# rtiduino.net
KiCad netlist of a schematic drawn in EAGLE
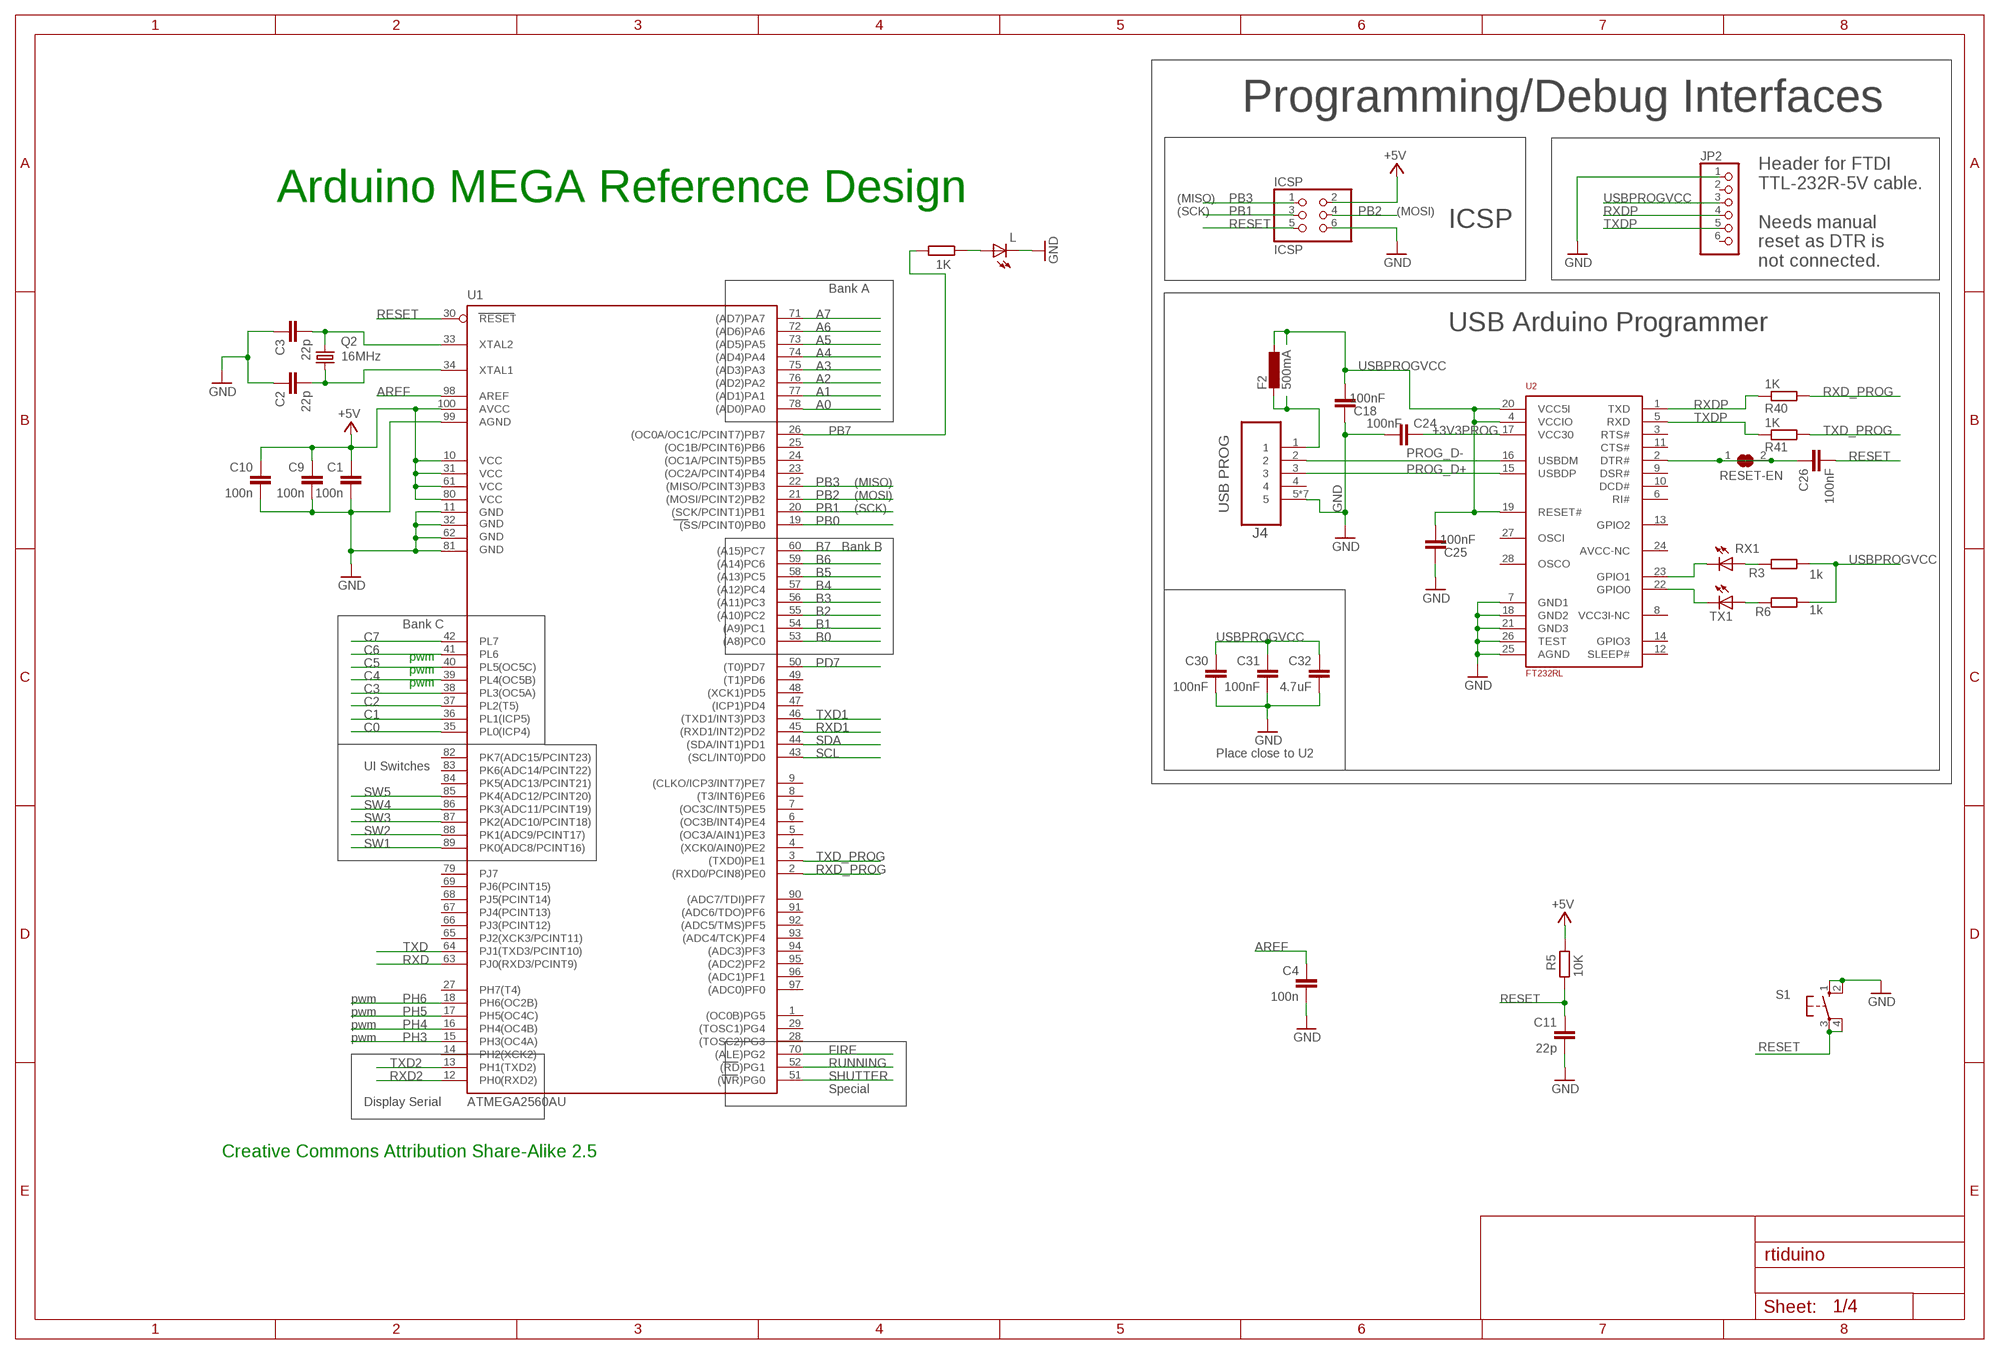
[diagram p0: schematic, sheet 1]
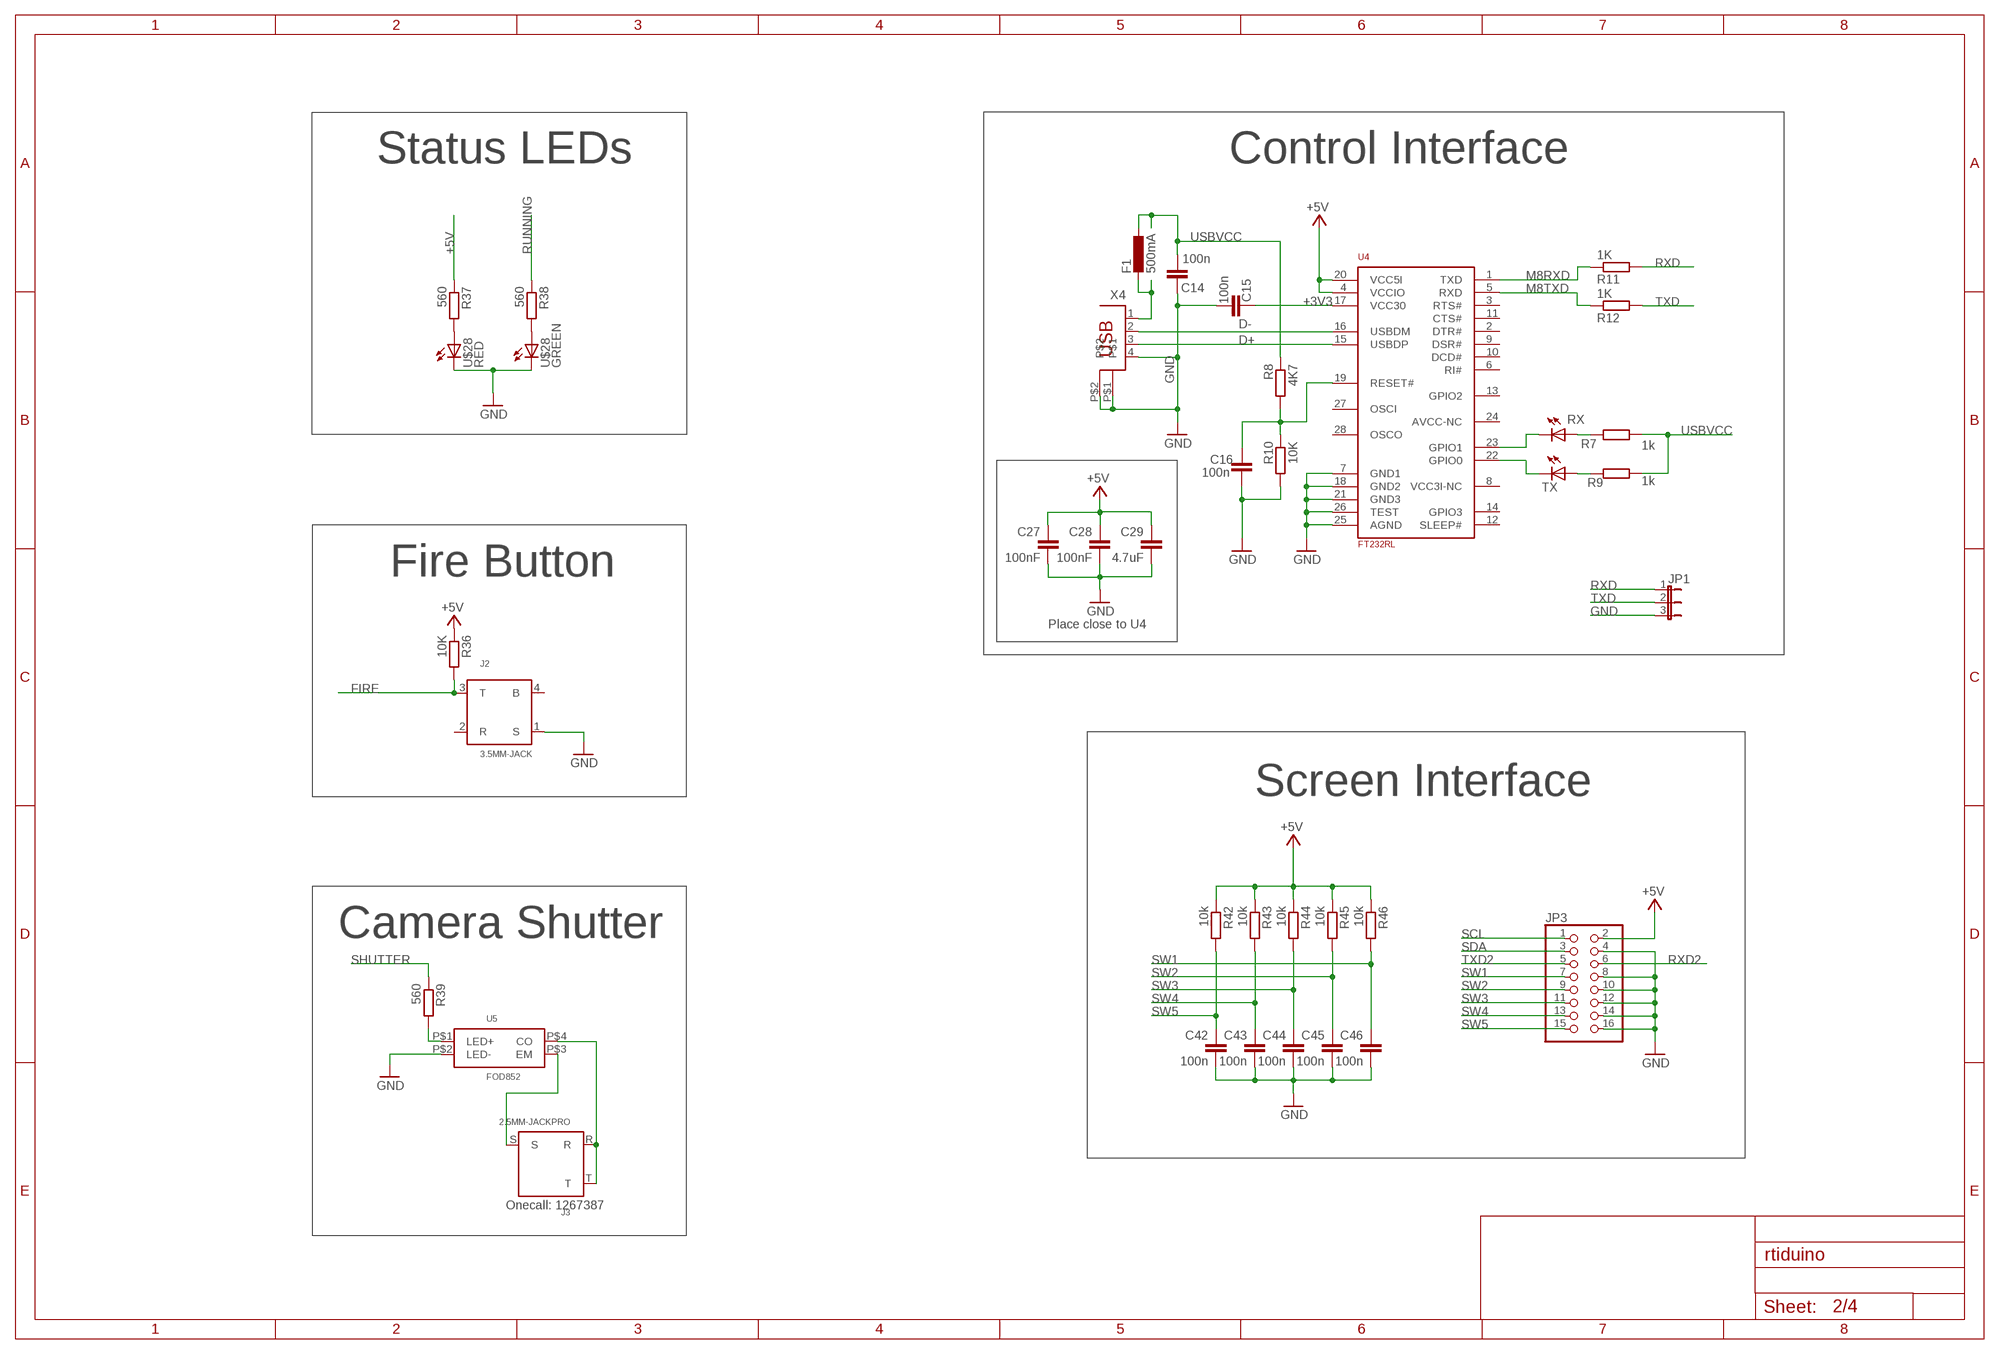
[diagram p1: schematic, sheet 2]
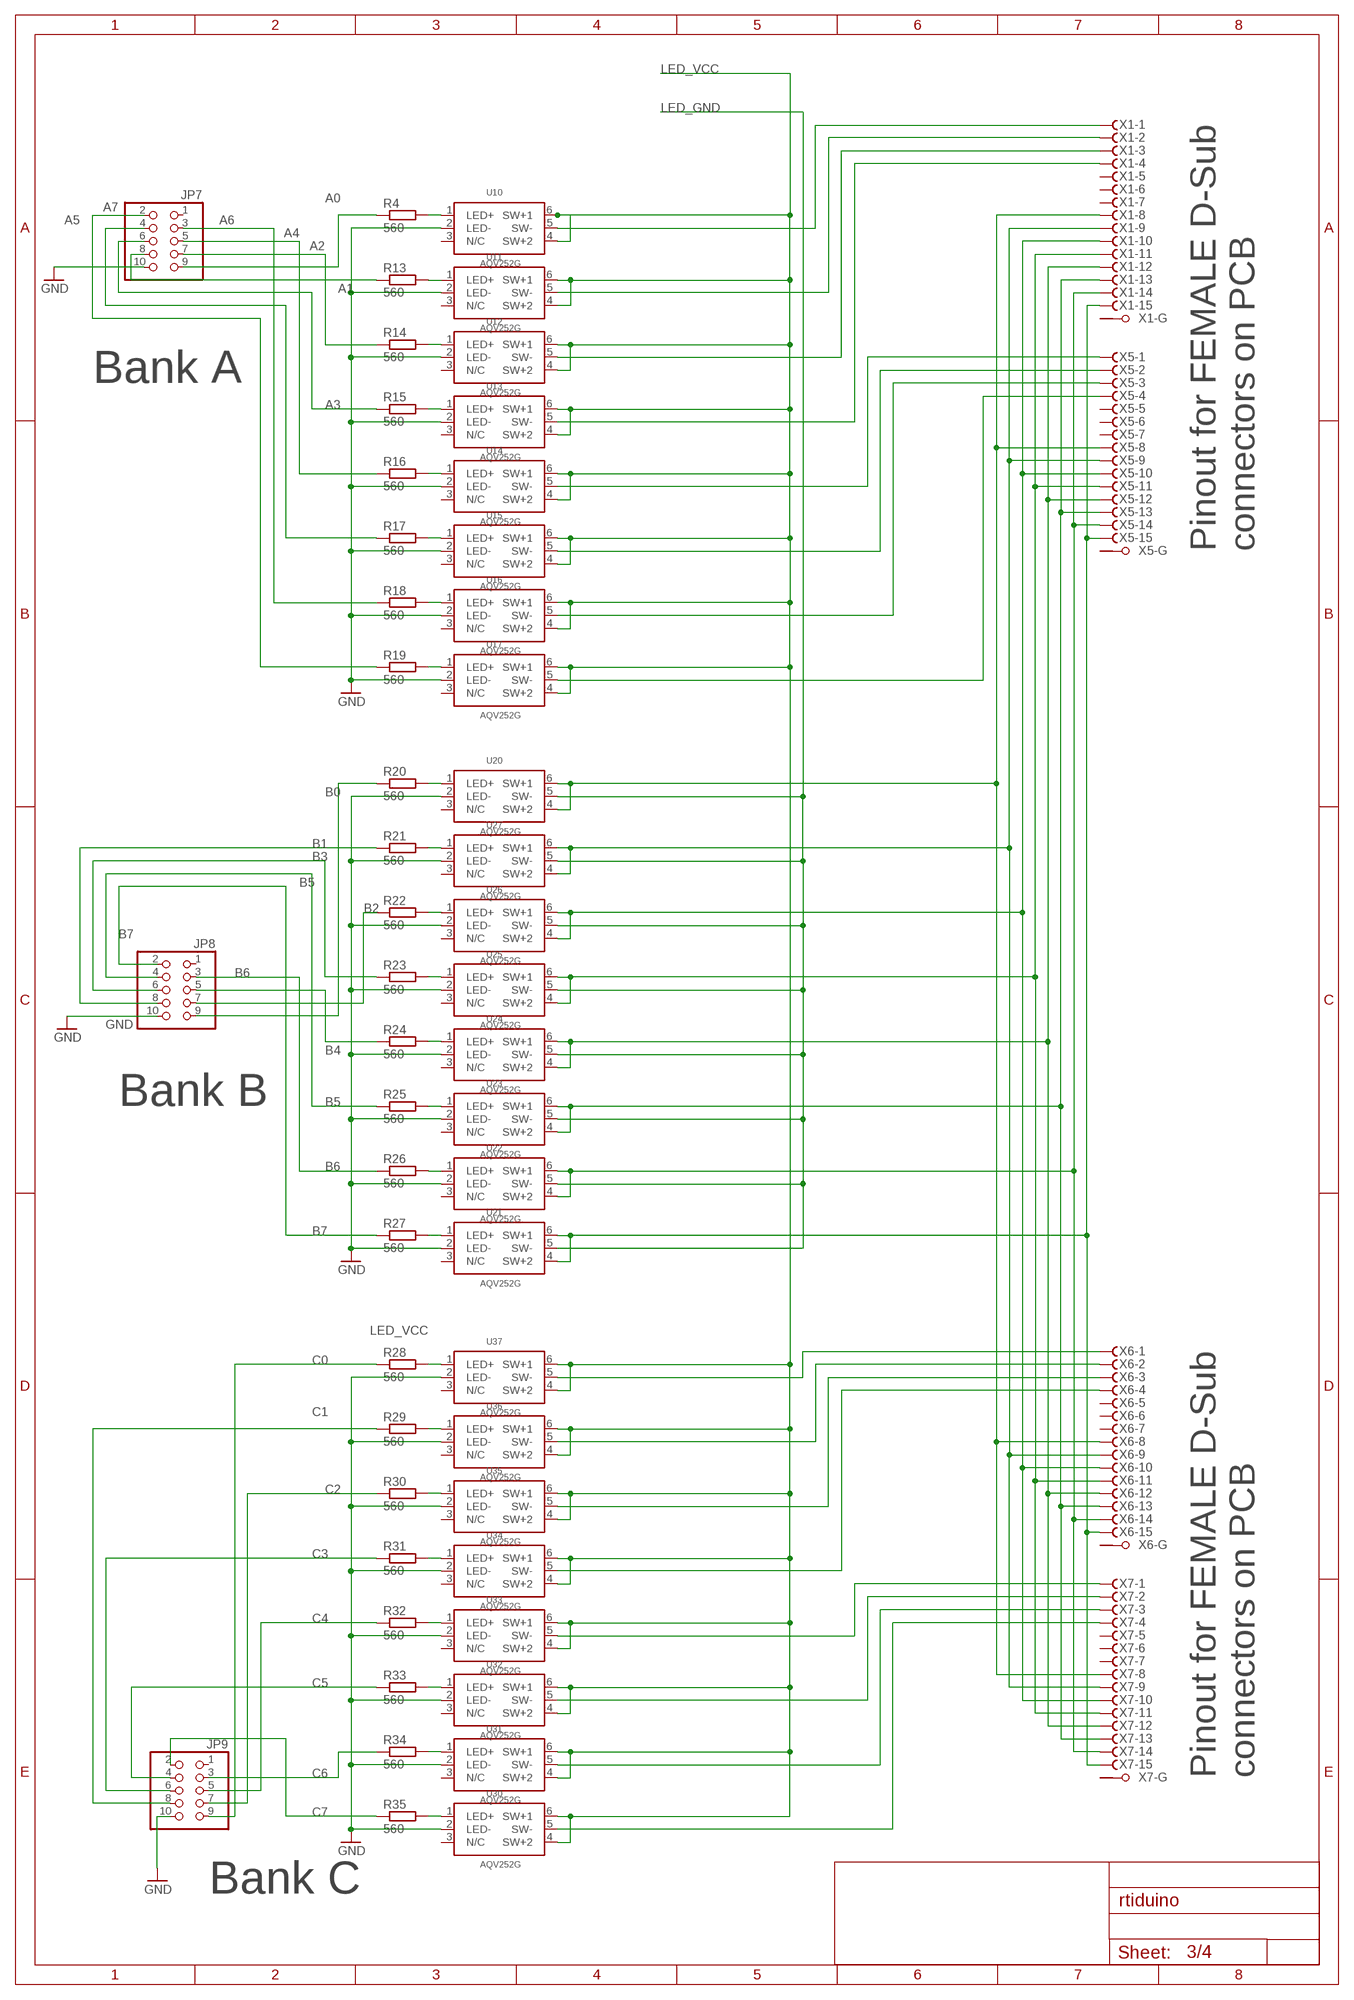
[diagram p2: schematic, sheet 3]
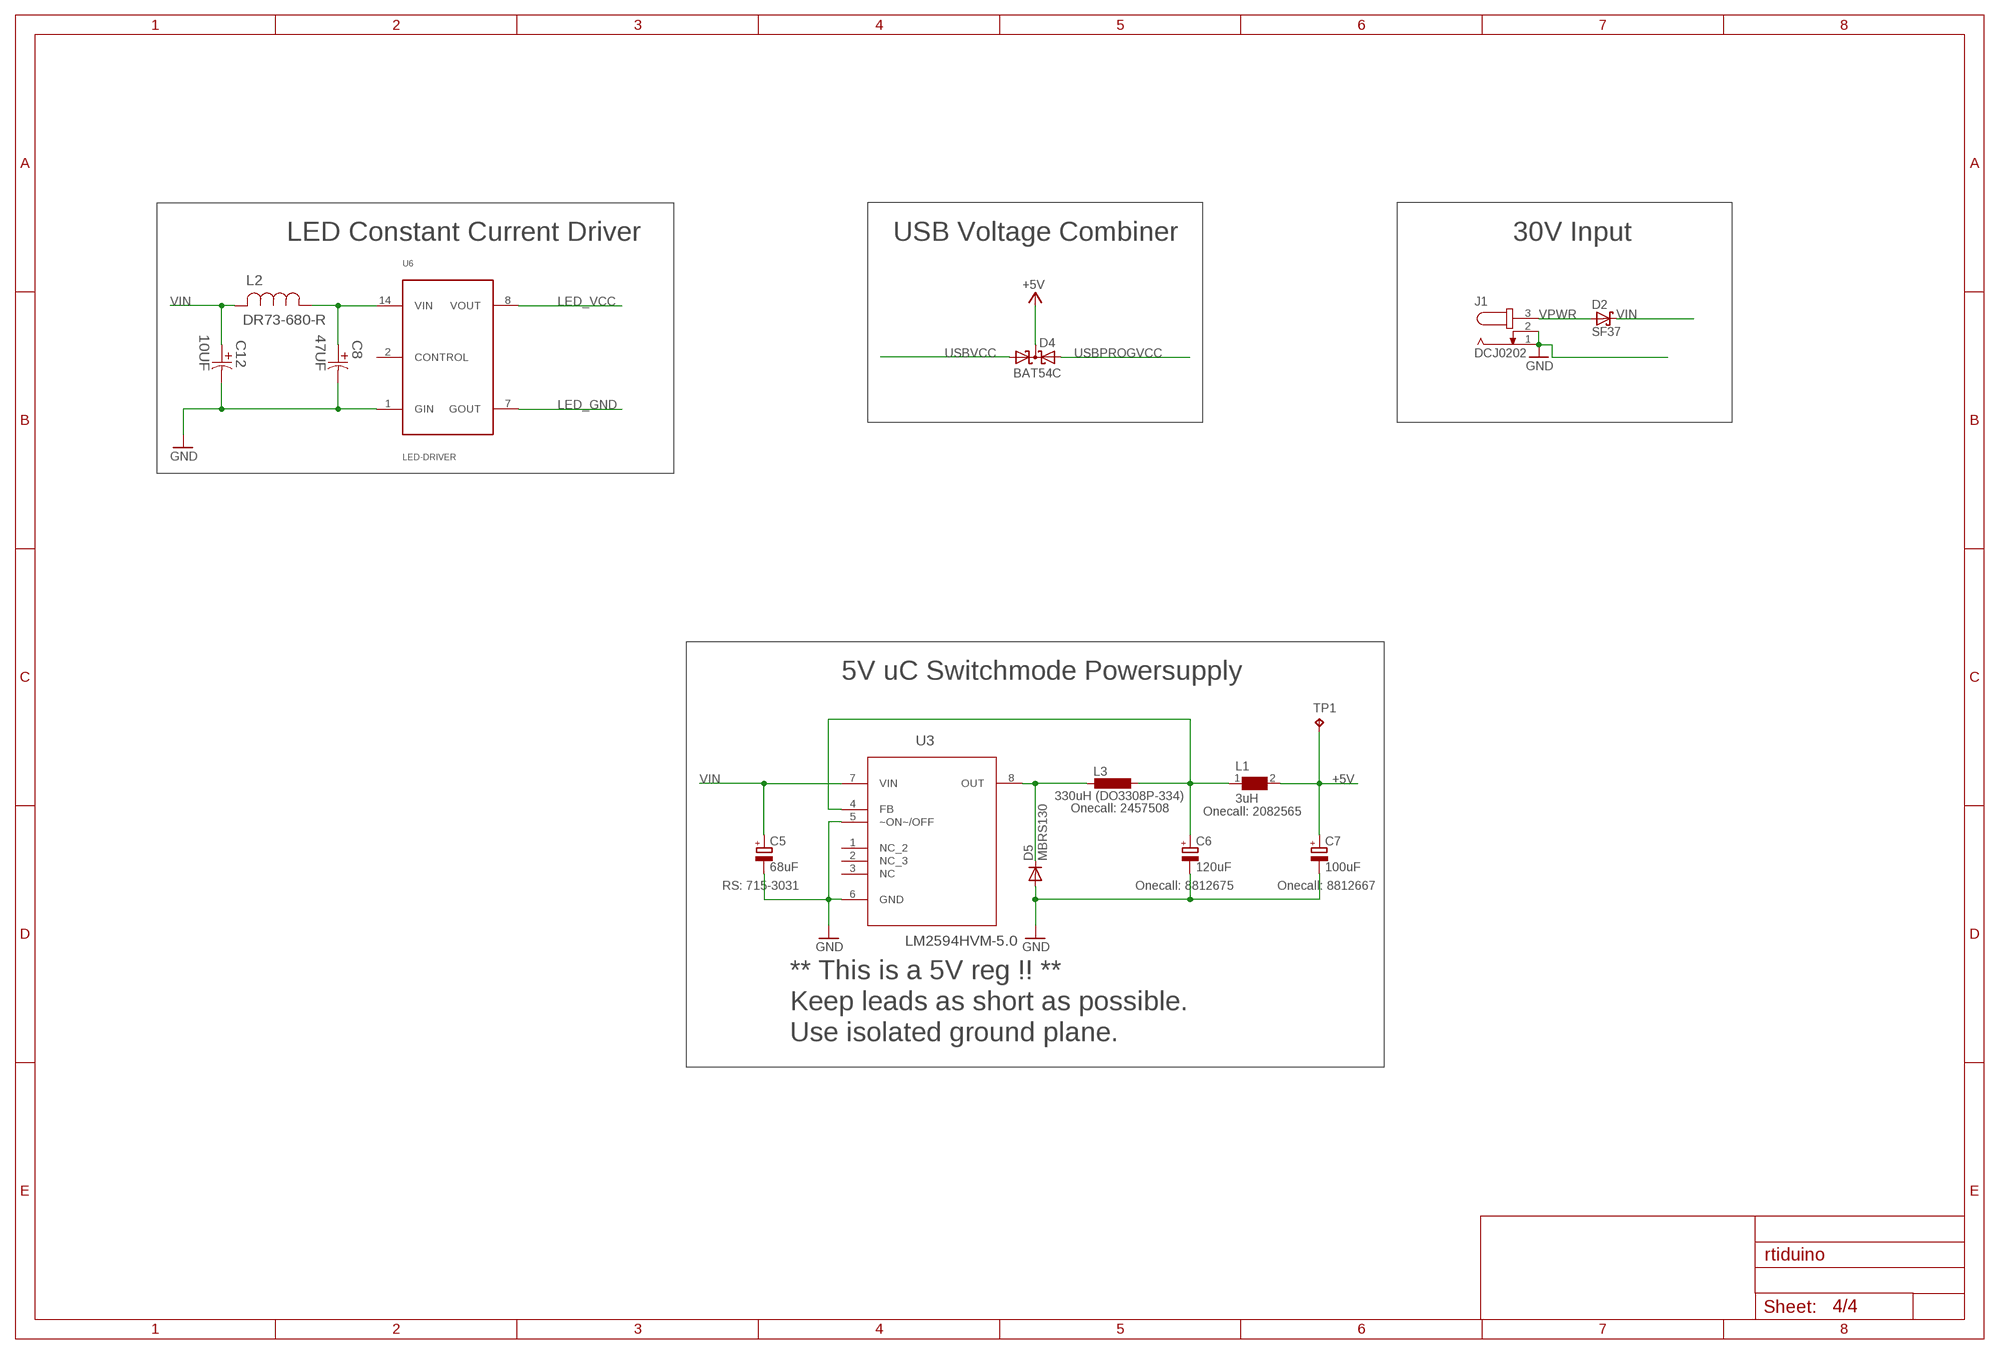
[diagram p3: schematic, sheet 4]

(export (version "E")
  (design (tool "Eeschema 10.0.6"))
  (components
    (comp (ref "C1")
      (value "100n")
      (footprint "eagle-import:C0805K")
      (libsource (lib "eagle-import") (part "C-EUC0805K"))
    )
    (comp (ref "C2")
      (value "22p")
      (footprint "eagle-import:C0805K")
      (libsource (lib "eagle-import") (part "C-EUC0805K"))
    )
    (comp (ref "C3")
      (value "22p")
      (footprint "eagle-import:C0805K")
      (libsource (lib "eagle-import") (part "C-EUC0805K"))
    )
    (comp (ref "C4")
      (value "100n")
      (footprint "eagle-import:C0805K")
      (libsource (lib "eagle-import") (part "C-EUC0805K"))
    )
    (comp (ref "C9")
      (value "100n")
      (footprint "eagle-import:C0805K")
      (libsource (lib "eagle-import") (part "C-EUC0805K"))
    )
    (comp (ref "C10")
      (value "100n")
      (footprint "eagle-import:C0805K")
      (libsource (lib "eagle-import") (part "C-EUC0805K"))
    )
    (comp (ref "C11")
      (value "22p")
      (footprint "eagle-import:C0805K")
      (libsource (lib "eagle-import") (part "C-EUC0805K"))
    )
    (comp (ref "C18")
      (value "100nF")
      (footprint "eagle-import:C0805K")
      (libsource (lib "eagle-import") (part "C-EUC0805K"))
    )
    (comp (ref "C24")
      (value "100nF")
      (footprint "eagle-import:C0805K")
      (libsource (lib "eagle-import") (part "C-EUC0805K"))
    )
    (comp (ref "C25")
      (value "100nF")
      (footprint "eagle-import:C0805K")
      (libsource (lib "eagle-import") (part "C-EUC0805K"))
    )
    (comp (ref "C26")
      (value "100nF")
      (footprint "eagle-import:C0805K")
      (libsource (lib "eagle-import") (part "C-EUC0805K"))
    )
    (comp (ref "C30")
      (value "100nF")
      (footprint "eagle-import:C0805K")
      (libsource (lib "eagle-import") (part "C-EUC0805K"))
    )
    (comp (ref "C31")
      (value "100nF")
      (footprint "eagle-import:C0805K")
      (libsource (lib "eagle-import") (part "C-EUC0805K"))
    )
    (comp (ref "C32")
      (value "4.7uF")
      (footprint "eagle-import:C0805K")
      (libsource (lib "eagle-import") (part "C-EUC0805K"))
    )
    (comp (ref "F2")
      (value "500mA")
      (footprint "eagle-import:L1812")
      (libsource (lib "eagle-import") (part "L-EUL1812"))
    )
    (comp (ref "ICSP")
      (value "ICSP")
      (footprint "eagle-import:2X03")
      (libsource (lib "eagle-import") (part "PINHD-2X3"))
    )
    (comp (ref "J4")
      (value "USB PROG")
      (footprint "eagle-import:MOLEX_47346-0001")
      (fields (field (name "MPN") "47346-0001"))
      (libsource (lib "eagle-import") (part "47346-0001"))
    )
    (comp (ref "JP2")
      (value "PINHD-1X6")
      (footprint "eagle-import:1X06")
      (libsource (lib "eagle-import") (part "PINHD-1X6"))
    )
    (comp (ref "L")
      (value "LED0805ROUND")
      (footprint "eagle-import:0805RND")
      (libsource (lib "eagle-import") (part "LED0805ROUND"))
    )
    (comp (ref "Q2")
      (value "16MHz")
      (footprint "eagle-import:HC49_S")
      (libsource (lib "eagle-import") (part "CRYTALHC49S"))
    )
    (comp (ref "R1")
      (value "1K")
      (footprint "eagle-import:R0805")
      (libsource (lib "eagle-import") (part "R-EU_R0805"))
    )
    (comp (ref "R3")
      (value "1k")
      (footprint "eagle-import:R0805")
      (libsource (lib "eagle-import") (part "R-EU_R0805"))
    )
    (comp (ref "R5")
      (value "10K")
      (footprint "eagle-import:R0805")
      (libsource (lib "eagle-import") (part "R-EU_R0805"))
    )
    (comp (ref "R6")
      (value "1k")
      (footprint "eagle-import:R0805")
      (libsource (lib "eagle-import") (part "R-EU_R0805"))
    )
    (comp (ref "R40")
      (value "1K")
      (footprint "eagle-import:R0805")
      (libsource (lib "eagle-import") (part "resistor_R-EU_R0805"))
    )
    (comp (ref "R41")
      (value "1K")
      (footprint "eagle-import:R0805")
      (libsource (lib "eagle-import") (part "resistor_R-EU_R0805"))
    )
    (comp (ref "RESET-EN")
      (value "SJ")
      (footprint "eagle-import:SJ")
      (libsource (lib "eagle-import") (part "SJ"))
    )
    (comp (ref "RX1")
      (value "LED0805ROUND")
      (footprint "eagle-import:0805RND")
      (libsource (lib "eagle-import") (part "LED0805ROUND"))
    )
    (comp (ref "S1")
      (value "10-XX")
      (footprint "eagle-import:B3F-10XX")
      (libsource (lib "eagle-import") (part "10-XX"))
    )
    (comp (ref "TX1")
      (value "LED0805ROUND")
      (footprint "eagle-import:0805RND")
      (libsource (lib "eagle-import") (part "LED0805ROUND"))
    )
    (comp (ref "U1")
      (value "ATMEGA2560AU")
      (footprint "eagle-import:TQFP100")
      (libsource (lib "eagle-import") (part "ATMEGA2560AU"))
    )
    (comp (ref "U2")
      (value "FT232RL")
      (footprint "eagle-import:SSOP28")
      (libsource (lib "eagle-import") (part "FT232RL"))
    )
    (comp (ref "C14")
      (value "100n")
      (footprint "eagle-import:C0805K")
      (libsource (lib "eagle-import") (part "C-EUC0805K"))
    )
    (comp (ref "C15")
      (value "100n")
      (footprint "eagle-import:C0805K")
      (libsource (lib "eagle-import") (part "C-EUC0805K"))
    )
    (comp (ref "C16")
      (value "100n")
      (footprint "eagle-import:C0805K")
      (libsource (lib "eagle-import") (part "C-EUC0805K"))
    )
    (comp (ref "C27")
      (value "100nF")
      (footprint "eagle-import:C0805K")
      (libsource (lib "eagle-import") (part "C-EUC0805K"))
    )
    (comp (ref "C28")
      (value "100nF")
      (footprint "eagle-import:C0805K")
      (libsource (lib "eagle-import") (part "C-EUC0805K"))
    )
    (comp (ref "C29")
      (value "4.7uF")
      (footprint "eagle-import:C0805K")
      (libsource (lib "eagle-import") (part "C-EUC0805K"))
    )
    (comp (ref "C42")
      (value "100n")
      (footprint "eagle-import:C0805K")
      (libsource (lib "eagle-import") (part "C-EUC0805K"))
    )
    (comp (ref "C43")
      (value "100n")
      (footprint "eagle-import:C0805K")
      (libsource (lib "eagle-import") (part "C-EUC0805K"))
    )
    (comp (ref "C44")
      (value "100n")
      (footprint "eagle-import:C0805K")
      (libsource (lib "eagle-import") (part "C-EUC0805K"))
    )
    (comp (ref "C45")
      (value "100n")
      (footprint "eagle-import:C0805K")
      (libsource (lib "eagle-import") (part "C-EUC0805K"))
    )
    (comp (ref "C46")
      (value "100n")
      (footprint "eagle-import:C0805K")
      (libsource (lib "eagle-import") (part "C-EUC0805K"))
    )
    (comp (ref "F1")
      (value "500mA")
      (footprint "eagle-import:L1812")
      (libsource (lib "eagle-import") (part "L-EUL1812"))
    )
    (comp (ref "J2")
      (value "3.5MM-JACK")
      (footprint "eagle-import:3.5-JACK-RA")
      (libsource (lib "eagle-import") (part "3.5MM-JACK"))
    )
    (comp (ref "J3")
      (value "2.5MM-JACKPRO")
      (footprint "eagle-import:2.5-JACK-RA-PRO")
      (libsource (lib "eagle-import") (part "2.5MM-JACKPRO"))
    )
    (comp (ref "JP1")
      (value "JP2E")
      (footprint "eagle-import:JP2")
      (libsource (lib "eagle-import") (part "JP2E"))
    )
    (comp (ref "JP3")
      (value "PINHD-2X8")
      (footprint "eagle-import:2X08")
      (libsource (lib "eagle-import") (part "PINHD-2X8"))
    )
    (comp (ref "R7")
      (value "1k")
      (footprint "eagle-import:R0805")
      (libsource (lib "eagle-import") (part "R-EU_R0805"))
    )
    (comp (ref "R8")
      (value "4K7")
      (footprint "eagle-import:R0805")
      (libsource (lib "eagle-import") (part "resistor_R-EU_R0805"))
    )
    (comp (ref "R9")
      (value "1k")
      (footprint "eagle-import:R0805")
      (libsource (lib "eagle-import") (part "R-EU_R0805"))
    )
    (comp (ref "R10")
      (value "10K")
      (footprint "eagle-import:R0805")
      (libsource (lib "eagle-import") (part "resistor_R-EU_R0805"))
    )
    (comp (ref "R11")
      (value "1K")
      (footprint "eagle-import:R0805")
      (libsource (lib "eagle-import") (part "resistor_R-EU_R0805"))
    )
    (comp (ref "R12")
      (value "1K")
      (footprint "eagle-import:R0805")
      (libsource (lib "eagle-import") (part "resistor_R-EU_R0805"))
    )
    (comp (ref "R36")
      (value "10K")
      (footprint "eagle-import:R0805")
      (libsource (lib "eagle-import") (part "resistor_R-EU_R0805"))
    )
    (comp (ref "R37")
      (value "560")
      (footprint "eagle-import:R0805")
      (libsource (lib "eagle-import") (part "resistor_R-EU_R0805"))
    )
    (comp (ref "R38")
      (value "560")
      (footprint "eagle-import:R0805")
      (libsource (lib "eagle-import") (part "resistor_R-EU_R0805"))
    )
    (comp (ref "R39")
      (value "560")
      (footprint "eagle-import:R0805")
      (libsource (lib "eagle-import") (part "resistor_R-EU_R0805"))
    )
    (comp (ref "R42")
      (value "10k")
      (footprint "eagle-import:R0805")
      (libsource (lib "eagle-import") (part "resistor_R-EU_R0805"))
    )
    (comp (ref "R43")
      (value "10k")
      (footprint "eagle-import:R0805")
      (libsource (lib "eagle-import") (part "resistor_R-EU_R0805"))
    )
    (comp (ref "R44")
      (value "10k")
      (footprint "eagle-import:R0805")
      (libsource (lib "eagle-import") (part "resistor_R-EU_R0805"))
    )
    (comp (ref "R45")
      (value "10k")
      (footprint "eagle-import:R0805")
      (libsource (lib "eagle-import") (part "resistor_R-EU_R0805"))
    )
    (comp (ref "R46")
      (value "10k")
      (footprint "eagle-import:R0805")
      (libsource (lib "eagle-import") (part "resistor_R-EU_R0805"))
    )
    (comp (ref "RX")
      (value "LED0805ROUND")
      (footprint "eagle-import:0805RND")
      (libsource (lib "eagle-import") (part "LED0805ROUND"))
    )
    (comp (ref "TX")
      (value "LED0805ROUND")
      (footprint "eagle-import:0805RND")
      (libsource (lib "eagle-import") (part "LED0805ROUND"))
    )
    (comp (ref "U$28")
      (value "122-000-04-52")
      (footprint "eagle-import:122-000-04-52")
      (libsource (lib "eagle-import") (part "122-000-04-52"))
    )
    (comp (ref "U4")
      (value "FT232RL")
      (footprint "eagle-import:SSOP28")
      (libsource (lib "eagle-import") (part "FT232RL"))
    )
    (comp (ref "U5")
      (value "FOD852")
      (footprint "eagle-import:DIP4-SMD")
      (libsource (lib "eagle-import") (part "FOD852"))
    )
    (comp (ref "X4")
      (value "PN61729")
      (footprint "eagle-import:PN61729")
      (libsource (lib "eagle-import") (part "PN61729"))
    )
    (comp (ref "JP7")
      (value "PINHD-2X5")
      (footprint "eagle-import:2X05")
      (libsource (lib "eagle-import") (part "PINHD-2X5"))
    )
    (comp (ref "JP8")
      (value "PINHD-2X5")
      (footprint "eagle-import:2X05")
      (libsource (lib "eagle-import") (part "PINHD-2X5"))
    )
    (comp (ref "JP9")
      (value "PINHD-2X5")
      (footprint "eagle-import:2X05")
      (libsource (lib "eagle-import") (part "PINHD-2X5"))
    )
    (comp (ref "R4")
      (value "560")
      (footprint "eagle-import:R0805")
      (libsource (lib "eagle-import") (part "R-EU_R0805"))
    )
    (comp (ref "R13")
      (value "560")
      (footprint "eagle-import:R0805")
      (libsource (lib "eagle-import") (part "R-EU_R0805"))
    )
    (comp (ref "R14")
      (value "560")
      (footprint "eagle-import:R0805")
      (libsource (lib "eagle-import") (part "R-EU_R0805"))
    )
    (comp (ref "R15")
      (value "560")
      (footprint "eagle-import:R0805")
      (libsource (lib "eagle-import") (part "R-EU_R0805"))
    )
    (comp (ref "R16")
      (value "560")
      (footprint "eagle-import:R0805")
      (libsource (lib "eagle-import") (part "R-EU_R0805"))
    )
    (comp (ref "R17")
      (value "560")
      (footprint "eagle-import:R0805")
      (libsource (lib "eagle-import") (part "R-EU_R0805"))
    )
    (comp (ref "R18")
      (value "560")
      (footprint "eagle-import:R0805")
      (libsource (lib "eagle-import") (part "R-EU_R0805"))
    )
    (comp (ref "R19")
      (value "560")
      (footprint "eagle-import:R0805")
      (libsource (lib "eagle-import") (part "R-EU_R0805"))
    )
    (comp (ref "R20")
      (value "560")
      (footprint "eagle-import:R0805")
      (libsource (lib "eagle-import") (part "R-EU_R0805"))
    )
    (comp (ref "R21")
      (value "560")
      (footprint "eagle-import:R0805")
      (libsource (lib "eagle-import") (part "R-EU_R0805"))
    )
    (comp (ref "R22")
      (value "560")
      (footprint "eagle-import:R0805")
      (libsource (lib "eagle-import") (part "R-EU_R0805"))
    )
    (comp (ref "R23")
      (value "560")
      (footprint "eagle-import:R0805")
      (libsource (lib "eagle-import") (part "R-EU_R0805"))
    )
    (comp (ref "R24")
      (value "560")
      (footprint "eagle-import:R0805")
      (libsource (lib "eagle-import") (part "R-EU_R0805"))
    )
    (comp (ref "R25")
      (value "560")
      (footprint "eagle-import:R0805")
      (libsource (lib "eagle-import") (part "R-EU_R0805"))
    )
    (comp (ref "R26")
      (value "560")
      (footprint "eagle-import:R0805")
      (libsource (lib "eagle-import") (part "R-EU_R0805"))
    )
    (comp (ref "R27")
      (value "560")
      (footprint "eagle-import:R0805")
      (libsource (lib "eagle-import") (part "R-EU_R0805"))
    )
    (comp (ref "R28")
      (value "560")
      (footprint "eagle-import:R0805")
      (libsource (lib "eagle-import") (part "R-EU_R0805"))
    )
    (comp (ref "R29")
      (value "560")
      (footprint "eagle-import:R0805")
      (libsource (lib "eagle-import") (part "R-EU_R0805"))
    )
    (comp (ref "R30")
      (value "560")
      (footprint "eagle-import:R0805")
      (libsource (lib "eagle-import") (part "R-EU_R0805"))
    )
    (comp (ref "R31")
      (value "560")
      (footprint "eagle-import:R0805")
      (libsource (lib "eagle-import") (part "R-EU_R0805"))
    )
    (comp (ref "R32")
      (value "560")
      (footprint "eagle-import:R0805")
      (libsource (lib "eagle-import") (part "R-EU_R0805"))
    )
    (comp (ref "R33")
      (value "560")
      (footprint "eagle-import:R0805")
      (libsource (lib "eagle-import") (part "R-EU_R0805"))
    )
    (comp (ref "R34")
      (value "560")
      (footprint "eagle-import:R0805")
      (libsource (lib "eagle-import") (part "R-EU_R0805"))
    )
    (comp (ref "R35")
      (value "560")
      (footprint "eagle-import:R0805")
      (libsource (lib "eagle-import") (part "R-EU_R0805"))
    )
    (comp (ref "U10")
      (value "AQV252G")
      (footprint "eagle-import:SOP6")
      (libsource (lib "eagle-import") (part "AQV252G"))
    )
    (comp (ref "U11")
      (value "AQV252G")
      (footprint "eagle-import:SOP6")
      (libsource (lib "eagle-import") (part "AQV252G"))
    )
    (comp (ref "U12")
      (value "AQV252G")
      (footprint "eagle-import:SOP6")
      (libsource (lib "eagle-import") (part "AQV252G"))
    )
    (comp (ref "U13")
      (value "AQV252G")
      (footprint "eagle-import:SOP6")
      (libsource (lib "eagle-import") (part "AQV252G"))
    )
    (comp (ref "U14")
      (value "AQV252G")
      (footprint "eagle-import:SOP6")
      (libsource (lib "eagle-import") (part "AQV252G"))
    )
    (comp (ref "U15")
      (value "AQV252G")
      (footprint "eagle-import:SOP6")
      (libsource (lib "eagle-import") (part "AQV252G"))
    )
    (comp (ref "U16")
      (value "AQV252G")
      (footprint "eagle-import:SOP6")
      (libsource (lib "eagle-import") (part "AQV252G"))
    )
    (comp (ref "U17")
      (value "AQV252G")
      (footprint "eagle-import:SOP6")
      (libsource (lib "eagle-import") (part "AQV252G"))
    )
    (comp (ref "U20")
      (value "AQV252G")
      (footprint "eagle-import:SOP6")
      (libsource (lib "eagle-import") (part "AQV252G"))
    )
    (comp (ref "U21")
      (value "AQV252G")
      (footprint "eagle-import:SOP6")
      (libsource (lib "eagle-import") (part "AQV252G"))
    )
    (comp (ref "U22")
      (value "AQV252G")
      (footprint "eagle-import:SOP6")
      (libsource (lib "eagle-import") (part "AQV252G"))
    )
    (comp (ref "U23")
      (value "AQV252G")
      (footprint "eagle-import:SOP6")
      (libsource (lib "eagle-import") (part "AQV252G"))
    )
    (comp (ref "U24")
      (value "AQV252G")
      (footprint "eagle-import:SOP6")
      (libsource (lib "eagle-import") (part "AQV252G"))
    )
    (comp (ref "U25")
      (value "AQV252G")
      (footprint "eagle-import:SOP6")
      (libsource (lib "eagle-import") (part "AQV252G"))
    )
    (comp (ref "U26")
      (value "AQV252G")
      (footprint "eagle-import:SOP6")
      (libsource (lib "eagle-import") (part "AQV252G"))
    )
    (comp (ref "U27")
      (value "AQV252G")
      (footprint "eagle-import:SOP6")
      (libsource (lib "eagle-import") (part "AQV252G"))
    )
    (comp (ref "U30")
      (value "AQV252G")
      (footprint "eagle-import:SOP6")
      (libsource (lib "eagle-import") (part "AQV252G"))
    )
    (comp (ref "U31")
      (value "AQV252G")
      (footprint "eagle-import:SOP6")
      (libsource (lib "eagle-import") (part "AQV252G"))
    )
    (comp (ref "U32")
      (value "AQV252G")
      (footprint "eagle-import:SOP6")
      (libsource (lib "eagle-import") (part "AQV252G"))
    )
    (comp (ref "U33")
      (value "AQV252G")
      (footprint "eagle-import:SOP6")
      (libsource (lib "eagle-import") (part "AQV252G"))
    )
    (comp (ref "U34")
      (value "AQV252G")
      (footprint "eagle-import:SOP6")
      (libsource (lib "eagle-import") (part "AQV252G"))
    )
    (comp (ref "U35")
      (value "AQV252G")
      (footprint "eagle-import:SOP6")
      (libsource (lib "eagle-import") (part "AQV252G"))
    )
    (comp (ref "U36")
      (value "AQV252G")
      (footprint "eagle-import:SOP6")
      (libsource (lib "eagle-import") (part "AQV252G"))
    )
    (comp (ref "U37")
      (value "AQV252G")
      (footprint "eagle-import:SOP6")
      (libsource (lib "eagle-import") (part "AQV252G"))
    )
    (comp (ref "X1")
      (value "F15HPS")
      (footprint "eagle-import:F15HP")
      (libsource (lib "eagle-import") (part "F15HPS"))
    )
    (comp (ref "X5")
      (value "F15HPS")
      (footprint "eagle-import:F15HP")
      (libsource (lib "eagle-import") (part "F15HPS"))
    )
    (comp (ref "X6")
      (value "F15HPS")
      (footprint "eagle-import:F15HP")
      (libsource (lib "eagle-import") (part "F15HPS"))
    )
    (comp (ref "X7")
      (value "F15HPS")
      (footprint "eagle-import:F15HP")
      (libsource (lib "eagle-import") (part "F15HPS"))
    )
    (comp (ref "C5")
      (value "68uF")
      (footprint "eagle-import:E5-13")
      (libsource (lib "eagle-import") (part "CPOL-EUE5-13"))
    )
    (comp (ref "C6")
      (value "120uF")
      (footprint "eagle-import:E5-13")
      (libsource (lib "eagle-import") (part "CPOL-EUE5-13"))
    )
    (comp (ref "C7")
      (value "100uF")
      (footprint "eagle-import:E5-13")
      (libsource (lib "eagle-import") (part "CPOL-EUE5-13"))
    )
    (comp (ref "C8")
      (value "47UF")
      (footprint "eagle-import:CAPAE830X1050N")
      (fields (field (name "MPN") "EEE-FK1J470P") (field (name "TOLERANCE") "±20 %"))
      (libsource (lib "eagle-import") (part "EEE--CASE-FFK1J470P"))
    )
    (comp (ref "C12")
      (value "10UF")
      (footprint "eagle-import:CAPAE660X610N")
      (fields (field (name "MPN") "EEE-FK1J100P") (field (name "TOLERANCE") "±20 %"))
      (libsource (lib "eagle-import") (part "EEE--CASE-DFK1J100P"))
    )
    (comp (ref "D2")
      (value "SF37")
      (footprint "eagle-import:DO-201AD")
      (libsource (lib "eagle-import") (part "SF37"))
    )
    (comp (ref "D4")
      (value "BAT54C")
      (footprint "eagle-import:SOT23")
      (libsource (lib "eagle-import") (part "BAT54C"))
    )
    (comp (ref "D5")
      (value "MBRS130")
      (footprint "eagle-import:DO214AA")
      (libsource (lib "eagle-import") (part "DIODE-DO214AA"))
    )
    (comp (ref "J1")
      (value "DCJ0202")
      (footprint "eagle-import:SPC4077")
      (libsource (lib "eagle-import") (part "JACK-PLUG0"))
    )
    (comp (ref "L1")
      (value "3uH")
      (footprint "eagle-import:WE-TPC_5818_5828")
      (fields (field (name "MPN") "744053003"))
      (libsource (lib "eagle-import") (part "WE-TPC_5818/5828-744053003"))
    )
    (comp (ref "L2")
      (value "DR73-680-R")
      (footprint "eagle-import:INDM7676X355N")
      (fields (field (name "TOLERANCE") "±20%"))
      (libsource (lib "eagle-import") (part "DR73-680-R"))
    )
    (comp (ref "L3")
      (value "330uH (DO3308P-334)")
      (footprint "eagle-import:DO3316P")
      (libsource (lib "eagle-import") (part "DO3316P"))
    )
    (comp (ref "TP1")
      (value "TPB2,54")
      (footprint "eagle-import:B2,54")
      (libsource (lib "eagle-import") (part "TPB2,54"))
    )
    (comp (ref "U3")
      (value "LM2594HVM-5.0")
      (footprint "eagle-import:SOIC127P620X175-8N")
      (fields (field (name "MPN") "LM2594HVM-33"))
      (libsource (lib "eagle-import") (part "LM2594HVM-3.3"))
    )
    (comp (ref "U6")
      (value "LED-DRIVER")
      (footprint "eagle-import:LDU08")
      (libsource (lib "eagle-import") (part "LED-DRIVER"))
    )
  )
  (nets
    (net (code "1") (name "+3V3") (class "Default")
      (node (ref "C15") (pin "2") (pinfunction "2_2") (pintype "passive"))
      (node (ref "U4") (pin "17") (pinfunction "VCC30_17") (pintype "power_in"))
    )
    (net (code "2") (name "+3V3PROG") (class "Default")
      (node (ref "C24") (pin "2") (pinfunction "2_2") (pintype "passive"))
      (node (ref "U2") (pin "17") (pinfunction "VCC30_17") (pintype "power_in"))
    )
    (net (code "3") (name "+5V") (class "Default")
      (node (ref "C1") (pin "1") (pinfunction "1_1") (pintype "passive"))
      (node (ref "C10") (pin "1") (pinfunction "1_1") (pintype "passive"))
      (node (ref "C27") (pin "1") (pinfunction "1_1") (pintype "passive"))
      (node (ref "C28") (pin "1") (pinfunction "1_1") (pintype "passive"))
      (node (ref "C29") (pin "1") (pinfunction "1_1") (pintype "passive"))
      (node (ref "C7") (pin "+") (pinfunction "+_+") (pintype "passive"))
      (node (ref "C9") (pin "1") (pinfunction "1_1") (pintype "passive"))
      (node (ref "D4") (pin "3") (pinfunction "CC_3") (pintype "passive"))
      (node (ref "ICSP") (pin "2") (pinfunction "2_2") (pintype "passive"))
      (node (ref "JP3") (pin "2") (pinfunction "2_2") (pintype "passive"))
      (node (ref "L1") (pin "2") (pinfunction "2_2") (pintype "passive"))
      (node (ref "R36") (pin "1") (pinfunction "1_1") (pintype "passive"))
      (node (ref "R37") (pin "1") (pinfunction "1_1") (pintype "passive"))
      (node (ref "R42") (pin "1") (pinfunction "1_1") (pintype "passive"))
      (node (ref "R43") (pin "1") (pinfunction "1_1") (pintype "passive"))
      (node (ref "R44") (pin "1") (pinfunction "1_1") (pintype "passive"))
      (node (ref "R45") (pin "1") (pinfunction "1_1") (pintype "passive"))
      (node (ref "R46") (pin "1") (pinfunction "1_1") (pintype "passive"))
      (node (ref "R5") (pin "2") (pinfunction "2_2") (pintype "passive"))
      (node (ref "TP1") (pin "TP") (pinfunction "TP_TP") (pintype "input"))
      (node (ref "U1") (pin "10") (pinfunction "VCC_10") (pintype "power_in"))
      (node (ref "U1") (pin "100") (pinfunction "AVCC_100") (pintype "power_in"))
      (node (ref "U1") (pin "31") (pinfunction "VCC1_31") (pintype "power_in"))
      (node (ref "U1") (pin "61") (pinfunction "VCC2_61") (pintype "power_in"))
      (node (ref "U1") (pin "80") (pinfunction "VCC3_80") (pintype "power_in"))
      (node (ref "U4") (pin "20") (pinfunction "VCC5I_20") (pintype "power_in"))
      (node (ref "U4") (pin "4") (pinfunction "VCCIO_4") (pintype "power_in"))
    )
    (net (code "4") (name "A0") (class "Default")
      (node (ref "JP7") (pin "9") (pinfunction "9_9") (pintype "passive"))
      (node (ref "R4") (pin "1") (pinfunction "1_1") (pintype "passive"))
      (node (ref "U1") (pin "78") (pinfunction "(AD0)PA0_78") (pintype "bidirectional"))
    )
    (net (code "5") (name "A1") (class "Default")
      (node (ref "JP7") (pin "8") (pinfunction "8_8") (pintype "passive"))
      (node (ref "R13") (pin "1") (pinfunction "1_1") (pintype "passive"))
      (node (ref "U1") (pin "77") (pinfunction "(AD1)PA1_77") (pintype "bidirectional"))
    )
    (net (code "6") (name "A2") (class "Default")
      (node (ref "JP7") (pin "7") (pinfunction "7_7") (pintype "passive"))
      (node (ref "R14") (pin "1") (pinfunction "1_1") (pintype "passive"))
      (node (ref "U1") (pin "76") (pinfunction "(AD2)PA2_76") (pintype "bidirectional"))
    )
    (net (code "7") (name "A3") (class "Default")
      (node (ref "JP7") (pin "6") (pinfunction "6_6") (pintype "passive"))
      (node (ref "R15") (pin "1") (pinfunction "1_1") (pintype "passive"))
      (node (ref "U1") (pin "75") (pinfunction "(AD3)PA3_75") (pintype "bidirectional"))
    )
    (net (code "8") (name "A4") (class "Default")
      (node (ref "JP7") (pin "5") (pinfunction "5_5") (pintype "passive"))
      (node (ref "R16") (pin "1") (pinfunction "1_1") (pintype "passive"))
      (node (ref "U1") (pin "74") (pinfunction "(AD4)PA4_74") (pintype "bidirectional"))
    )
    (net (code "9") (name "A5") (class "Default")
      (node (ref "JP7") (pin "4") (pinfunction "4_4") (pintype "passive"))
      (node (ref "R17") (pin "1") (pinfunction "1_1") (pintype "passive"))
      (node (ref "U1") (pin "73") (pinfunction "(AD5)PA5_73") (pintype "bidirectional"))
    )
    (net (code "10") (name "A6") (class "Default")
      (node (ref "JP7") (pin "3") (pinfunction "3_3") (pintype "passive"))
      (node (ref "R18") (pin "1") (pinfunction "1_1") (pintype "passive"))
      (node (ref "U1") (pin "72") (pinfunction "(AD6)PA6_72") (pintype "bidirectional"))
    )
    (net (code "11") (name "A7") (class "Default")
      (node (ref "JP7") (pin "2") (pinfunction "2_2") (pintype "passive"))
      (node (ref "R19") (pin "1") (pinfunction "1_1") (pintype "passive"))
      (node (ref "U1") (pin "71") (pinfunction "(AD7)PA7_71") (pintype "bidirectional"))
    )
    (net (code "12") (name "AREF") (class "Default")
      (node (ref "C4") (pin "1") (pinfunction "1_1") (pintype "passive"))
      (node (ref "U1") (pin "98") (pinfunction "AREF_98") (pintype "bidirectional"))
    )
    (net (code "13") (name "B0") (class "Default")
      (node (ref "JP8") (pin "9") (pinfunction "9_9") (pintype "passive"))
      (node (ref "R20") (pin "1") (pinfunction "1_1") (pintype "passive"))
      (node (ref "U1") (pin "53") (pinfunction "(A8)PC0_53") (pintype "bidirectional"))
    )
    (net (code "14") (name "B1") (class "Default")
      (node (ref "JP8") (pin "8") (pinfunction "8_8") (pintype "passive"))
      (node (ref "R21") (pin "1") (pinfunction "1_1") (pintype "passive"))
      (node (ref "U1") (pin "54") (pinfunction "(A9)PC1_54") (pintype "bidirectional"))
    )
    (net (code "15") (name "B2") (class "Default")
      (node (ref "JP8") (pin "7") (pinfunction "7_7") (pintype "passive"))
      (node (ref "R22") (pin "1") (pinfunction "1_1") (pintype "passive"))
      (node (ref "U1") (pin "55") (pinfunction "(A10)PC2_55") (pintype "bidirectional"))
    )
    (net (code "16") (name "B3") (class "Default")
      (node (ref "JP8") (pin "6") (pinfunction "6_6") (pintype "passive"))
      (node (ref "R23") (pin "1") (pinfunction "1_1") (pintype "passive"))
      (node (ref "U1") (pin "56") (pinfunction "(A11)PC3_56") (pintype "bidirectional"))
    )
    (net (code "17") (name "B4") (class "Default")
      (node (ref "JP8") (pin "5") (pinfunction "5_5") (pintype "passive"))
      (node (ref "R24") (pin "1") (pinfunction "1_1") (pintype "passive"))
      (node (ref "U1") (pin "57") (pinfunction "(A12)PC4_57") (pintype "bidirectional"))
    )
    (net (code "18") (name "B5") (class "Default")
      (node (ref "JP8") (pin "4") (pinfunction "4_4") (pintype "passive"))
      (node (ref "R25") (pin "1") (pinfunction "1_1") (pintype "passive"))
      (node (ref "U1") (pin "58") (pinfunction "(A13)PC5_58") (pintype "bidirectional"))
    )
    (net (code "19") (name "B6") (class "Default")
      (node (ref "JP8") (pin "3") (pinfunction "3_3") (pintype "passive"))
      (node (ref "R26") (pin "1") (pinfunction "1_1") (pintype "passive"))
      (node (ref "U1") (pin "59") (pinfunction "(A14)PC6_59") (pintype "bidirectional"))
    )
    (net (code "20") (name "B7") (class "Default")
      (node (ref "JP8") (pin "2") (pinfunction "2_2") (pintype "passive"))
      (node (ref "R27") (pin "1") (pinfunction "1_1") (pintype "passive"))
      (node (ref "U1") (pin "60") (pinfunction "(A15)PC7_60") (pintype "bidirectional"))
    )
    (net (code "21") (name "C0") (class "Default")
      (node (ref "JP9") (pin "9") (pinfunction "9_9") (pintype "passive"))
      (node (ref "R28") (pin "1") (pinfunction "1_1") (pintype "passive"))
      (node (ref "U1") (pin "35") (pinfunction "PL0(ICP4)_35") (pintype "bidirectional"))
    )
    (net (code "22") (name "C1") (class "Default")
      (node (ref "JP9") (pin "8") (pinfunction "8_8") (pintype "passive"))
      (node (ref "R29") (pin "1") (pinfunction "1_1") (pintype "passive"))
      (node (ref "U1") (pin "36") (pinfunction "PL1(ICP5)_36") (pintype "bidirectional"))
    )
    (net (code "23") (name "C2") (class "Default")
      (node (ref "JP9") (pin "7") (pinfunction "7_7") (pintype "passive"))
      (node (ref "R30") (pin "1") (pinfunction "1_1") (pintype "passive"))
      (node (ref "U1") (pin "37") (pinfunction "PL2(T5)_37") (pintype "bidirectional"))
    )
    (net (code "24") (name "C3") (class "Default")
      (node (ref "JP9") (pin "6") (pinfunction "6_6") (pintype "passive"))
      (node (ref "R31") (pin "1") (pinfunction "1_1") (pintype "passive"))
      (node (ref "U1") (pin "38") (pinfunction "PL3(OC5A)_38") (pintype "bidirectional"))
    )
    (net (code "25") (name "C4") (class "Default")
      (node (ref "JP9") (pin "5") (pinfunction "5_5") (pintype "passive"))
      (node (ref "R32") (pin "1") (pinfunction "1_1") (pintype "passive"))
      (node (ref "U1") (pin "39") (pinfunction "PL4(OC5B)_39") (pintype "bidirectional"))
    )
    (net (code "26") (name "C5") (class "Default")
      (node (ref "JP9") (pin "4") (pinfunction "4_4") (pintype "passive"))
      (node (ref "R33") (pin "1") (pinfunction "1_1") (pintype "passive"))
      (node (ref "U1") (pin "40") (pinfunction "PL5(OC5C)_40") (pintype "bidirectional"))
    )
    (net (code "27") (name "C6") (class "Default")
      (node (ref "JP9") (pin "3") (pinfunction "3_3") (pintype "passive"))
      (node (ref "R34") (pin "1") (pinfunction "1_1") (pintype "passive"))
      (node (ref "U1") (pin "41") (pinfunction "PL6_41") (pintype "bidirectional"))
    )
    (net (code "28") (name "C7") (class "Default")
      (node (ref "JP9") (pin "2") (pinfunction "2_2") (pintype "passive"))
      (node (ref "R35") (pin "1") (pinfunction "1_1") (pintype "passive"))
      (node (ref "U1") (pin "42") (pinfunction "PL7_42") (pintype "bidirectional"))
    )
    (net (code "29") (name "D+") (class "Default")
      (node (ref "U4") (pin "15") (pinfunction "USBDP_15") (pintype "bidirectional"))
      (node (ref "X4") (pin "3") (pinfunction "3_3") (pintype "bidirectional"))
    )
    (net (code "30") (name "D-") (class "Default")
      (node (ref "U4") (pin "16") (pinfunction "USBDM_16") (pintype "bidirectional"))
      (node (ref "X4") (pin "2") (pinfunction "2_2") (pintype "bidirectional"))
    )
    (net (code "31") (name "FIRE") (class "Default")
      (node (ref "J2") (pin "3") (pinfunction "T_3") (pintype "passive"))
      (node (ref "R36") (pin "2") (pinfunction "2_2") (pintype "passive"))
      (node (ref "U1") (pin "70") (pinfunction "(ALE)PG2_70") (pintype "bidirectional"))
    )
    (net (code "32") (name "GND") (class "Default")
      (node (ref "C1") (pin "2") (pinfunction "2_2") (pintype "passive"))
      (node (ref "C10") (pin "2") (pinfunction "2_2") (pintype "passive"))
      (node (ref "C11") (pin "2") (pinfunction "2_2") (pintype "passive"))
      (node (ref "C12") (pin "2") (pinfunction "2_2") (pintype "passive"))
      (node (ref "C14") (pin "2") (pinfunction "2_2") (pintype "passive"))
      (node (ref "C15") (pin "1") (pinfunction "1_1") (pintype "passive"))
      (node (ref "C16") (pin "1") (pinfunction "1_1") (pintype "passive"))
      (node (ref "C18") (pin "2") (pinfunction "2_2") (pintype "passive"))
      (node (ref "C2") (pin "1") (pinfunction "1_1") (pintype "passive"))
      (node (ref "C24") (pin "1") (pinfunction "1_1") (pintype "passive"))
      (node (ref "C25") (pin "2") (pinfunction "2_2") (pintype "passive"))
      (node (ref "C27") (pin "2") (pinfunction "2_2") (pintype "passive"))
      (node (ref "C28") (pin "2") (pinfunction "2_2") (pintype "passive"))
      (node (ref "C29") (pin "2") (pinfunction "2_2") (pintype "passive"))
      (node (ref "C3") (pin "1") (pinfunction "1_1") (pintype "passive"))
      (node (ref "C30") (pin "2") (pinfunction "2_2") (pintype "passive"))
      (node (ref "C31") (pin "2") (pinfunction "2_2") (pintype "passive"))
      (node (ref "C32") (pin "2") (pinfunction "2_2") (pintype "passive"))
      (node (ref "C4") (pin "2") (pinfunction "2_2") (pintype "passive"))
      (node (ref "C42") (pin "2") (pinfunction "2_2") (pintype "passive"))
      (node (ref "C43") (pin "2") (pinfunction "2_2") (pintype "passive"))
      (node (ref "C44") (pin "2") (pinfunction "2_2") (pintype "passive"))
      (node (ref "C45") (pin "2") (pinfunction "2_2") (pintype "passive"))
      (node (ref "C46") (pin "2") (pinfunction "2_2") (pintype "passive"))
      (node (ref "C5") (pin "-") (pinfunction "-_-") (pintype "passive"))
      (node (ref "C6") (pin "-") (pinfunction "-_-") (pintype "passive"))
      (node (ref "C7") (pin "-") (pinfunction "-_-") (pintype "passive"))
      (node (ref "C8") (pin "2") (pinfunction "2_2") (pintype "passive"))
      (node (ref "C9") (pin "2") (pinfunction "2_2") (pintype "passive"))
      (node (ref "D5") (pin "A") (pinfunction "A_A") (pintype "passive"))
      (node (ref "ICSP") (pin "6") (pinfunction "6_6") (pintype "passive"))
      (node (ref "J1") (pin "1") (pinfunction "1_1") (pintype "passive"))
      (node (ref "J1") (pin "2") (pinfunction "2_2") (pintype "passive"))
      (node (ref "J2") (pin "1") (pinfunction "S_1") (pintype "passive"))
      (node (ref "J4") (pin "5") (pinfunction "5_5") (pintype "power_in"))
      (node (ref "J4") (pin "M1") (pinfunction "5_M1") (pintype "power_in"))
      (node (ref "J4") (pin "M2") (pinfunction "5_M2") (pintype "power_in"))
      (node (ref "J4") (pin "M3") (pinfunction "5_M3") (pintype "power_in"))
      (node (ref "J4") (pin "M4") (pinfunction "5_M4") (pintype "power_in"))
      (node (ref "J4") (pin "M5") (pinfunction "5_M5") (pintype "power_in"))
      (node (ref "J4") (pin "M6") (pinfunction "5_M6") (pintype "power_in"))
      (node (ref "JP1") (pin "3") (pinfunction "3_3") (pintype "passive"))
      (node (ref "JP2") (pin "1") (pinfunction "1_1") (pintype "passive"))
      (node (ref "JP3") (pin "10") (pinfunction "10_10") (pintype "passive"))
      (node (ref "JP3") (pin "12") (pinfunction "12_12") (pintype "passive"))
      (node (ref "JP3") (pin "14") (pinfunction "14_14") (pintype "passive"))
      (node (ref "JP3") (pin "16") (pinfunction "16_16") (pintype "passive"))
      (node (ref "JP3") (pin "4") (pinfunction "4_4") (pintype "passive"))
      (node (ref "JP3") (pin "8") (pinfunction "8_8") (pintype "passive"))
      (node (ref "JP7") (pin "10") (pinfunction "10_10") (pintype "passive"))
      (node (ref "JP8") (pin "10") (pinfunction "10_10") (pintype "passive"))
      (node (ref "JP9") (pin "10") (pinfunction "10_10") (pintype "passive"))
      (node (ref "L") (pin "P$2") (pinfunction "C_P$2") (pintype "passive"))
      (node (ref "R10") (pin "2") (pinfunction "2_2") (pintype "passive"))
      (node (ref "S1") (pin "1") (pinfunction "S_1") (pintype "passive"))
      (node (ref "S1") (pin "2") (pinfunction "S1_2") (pintype "passive"))
      (node (ref "U$28") (pin "P$1") (pinfunction "RC_P$1") (pintype "passive"))
      (node (ref "U$28") (pin "P$3") (pinfunction "GC_P$3") (pintype "passive"))
      (node (ref "U1") (pin "11") (pinfunction "GND_11") (pintype "power_in"))
      (node (ref "U1") (pin "32") (pinfunction "GND1_32") (pintype "power_in"))
      (node (ref "U1") (pin "62") (pinfunction "GND2_62") (pintype "power_in"))
      (node (ref "U1") (pin "81") (pinfunction "GND3_81") (pintype "power_in"))
      (node (ref "U1") (pin "99") (pinfunction "AGND_99") (pintype "power_in"))
      (node (ref "U10") (pin "2") (pinfunction "LED-_2") (pintype "bidirectional"))
      (node (ref "U11") (pin "2") (pinfunction "LED-_2") (pintype "bidirectional"))
      (node (ref "U12") (pin "2") (pinfunction "LED-_2") (pintype "bidirectional"))
      (node (ref "U13") (pin "2") (pinfunction "LED-_2") (pintype "bidirectional"))
      (node (ref "U14") (pin "2") (pinfunction "LED-_2") (pintype "bidirectional"))
      (node (ref "U15") (pin "2") (pinfunction "LED-_2") (pintype "bidirectional"))
      (node (ref "U16") (pin "2") (pinfunction "LED-_2") (pintype "bidirectional"))
      (node (ref "U17") (pin "2") (pinfunction "LED-_2") (pintype "bidirectional"))
      (node (ref "U2") (pin "18") (pinfunction "GND2_18") (pintype "power_in"))
      (node (ref "U2") (pin "21") (pinfunction "GND3_21") (pintype "power_in"))
      (node (ref "U2") (pin "25") (pinfunction "AGND_25") (pintype "power_in"))
      (node (ref "U2") (pin "26") (pinfunction "TEST_26") (pintype "input"))
      (node (ref "U2") (pin "7") (pinfunction "GND1_7") (pintype "power_in"))
      (node (ref "U20") (pin "2") (pinfunction "LED-_2") (pintype "bidirectional"))
      (node (ref "U21") (pin "2") (pinfunction "LED-_2") (pintype "bidirectional"))
      (node (ref "U22") (pin "2") (pinfunction "LED-_2") (pintype "bidirectional"))
      (node (ref "U23") (pin "2") (pinfunction "LED-_2") (pintype "bidirectional"))
      (node (ref "U24") (pin "2") (pinfunction "LED-_2") (pintype "bidirectional"))
      (node (ref "U25") (pin "2") (pinfunction "LED-_2") (pintype "bidirectional"))
      (node (ref "U26") (pin "2") (pinfunction "LED-_2") (pintype "bidirectional"))
      (node (ref "U27") (pin "2") (pinfunction "LED-_2") (pintype "bidirectional"))
      (node (ref "U3") (pin "5") (pinfunction "~{ON}/OFF_5") (pintype "input"))
      (node (ref "U3") (pin "6") (pinfunction "GND_6") (pintype "passive"))
      (node (ref "U30") (pin "2") (pinfunction "LED-_2") (pintype "bidirectional"))
      (node (ref "U31") (pin "2") (pinfunction "LED-_2") (pintype "bidirectional"))
      (node (ref "U32") (pin "2") (pinfunction "LED-_2") (pintype "bidirectional"))
      (node (ref "U33") (pin "2") (pinfunction "LED-_2") (pintype "bidirectional"))
      (node (ref "U34") (pin "2") (pinfunction "LED-_2") (pintype "bidirectional"))
      (node (ref "U35") (pin "2") (pinfunction "LED-_2") (pintype "bidirectional"))
      (node (ref "U36") (pin "2") (pinfunction "LED-_2") (pintype "bidirectional"))
      (node (ref "U37") (pin "2") (pinfunction "LED-_2") (pintype "bidirectional"))
      (node (ref "U4") (pin "18") (pinfunction "GND2_18") (pintype "power_in"))
      (node (ref "U4") (pin "21") (pinfunction "GND3_21") (pintype "power_in"))
      (node (ref "U4") (pin "25") (pinfunction "AGND_25") (pintype "power_in"))
      (node (ref "U4") (pin "26") (pinfunction "TEST_26") (pintype "input"))
      (node (ref "U4") (pin "7") (pinfunction "GND1_7") (pintype "power_in"))
      (node (ref "U5") (pin "P$2") (pinfunction "LED-_P$2") (pintype "bidirectional"))
      (node (ref "U6") (pin "1") (pinfunction "GIN_1") (pintype "bidirectional"))
      (node (ref "X4") (pin "4") (pinfunction "4_4") (pintype "bidirectional"))
      (node (ref "X4") (pin "P$1") (pinfunction "P$1_P$1") (pintype "bidirectional"))
      (node (ref "X4") (pin "P$2") (pinfunction "P$2_P$2") (pintype "bidirectional"))
    )
    (net (code "33") (name "LED_GND") (class "Default")
      (node (ref "U20") (pin "5") (pinfunction "SW-_5") (pintype "bidirectional"))
      (node (ref "U21") (pin "5") (pinfunction "SW-_5") (pintype "bidirectional"))
      (node (ref "U22") (pin "5") (pinfunction "SW-_5") (pintype "bidirectional"))
      (node (ref "U23") (pin "5") (pinfunction "SW-_5") (pintype "bidirectional"))
      (node (ref "U24") (pin "5") (pinfunction "SW-_5") (pintype "bidirectional"))
      (node (ref "U25") (pin "5") (pinfunction "SW-_5") (pintype "bidirectional"))
      (node (ref "U26") (pin "5") (pinfunction "SW-_5") (pintype "bidirectional"))
      (node (ref "U27") (pin "5") (pinfunction "SW-_5") (pintype "bidirectional"))
      (node (ref "U6") (pin "7") (pinfunction "GOUT_7") (pintype "bidirectional"))
    )
    (net (code "34") (name "LED_VCC") (class "Default")
      (node (ref "U10") (pin "4") (pinfunction "SW+2_4") (pintype "bidirectional"))
      (node (ref "U10") (pin "6") (pinfunction "SW+1_6") (pintype "bidirectional"))
      (node (ref "U11") (pin "4") (pinfunction "SW+2_4") (pintype "bidirectional"))
      (node (ref "U11") (pin "6") (pinfunction "SW+1_6") (pintype "bidirectional"))
      (node (ref "U12") (pin "4") (pinfunction "SW+2_4") (pintype "bidirectional"))
      (node (ref "U12") (pin "6") (pinfunction "SW+1_6") (pintype "bidirectional"))
      (node (ref "U13") (pin "4") (pinfunction "SW+2_4") (pintype "bidirectional"))
      (node (ref "U13") (pin "6") (pinfunction "SW+1_6") (pintype "bidirectional"))
      (node (ref "U14") (pin "4") (pinfunction "SW+2_4") (pintype "bidirectional"))
      (node (ref "U14") (pin "6") (pinfunction "SW+1_6") (pintype "bidirectional"))
      (node (ref "U15") (pin "4") (pinfunction "SW+2_4") (pintype "bidirectional"))
      (node (ref "U15") (pin "6") (pinfunction "SW+1_6") (pintype "bidirectional"))
      (node (ref "U16") (pin "4") (pinfunction "SW+2_4") (pintype "bidirectional"))
      (node (ref "U16") (pin "6") (pinfunction "SW+1_6") (pintype "bidirectional"))
      (node (ref "U17") (pin "4") (pinfunction "SW+2_4") (pintype "bidirectional"))
      (node (ref "U17") (pin "6") (pinfunction "SW+1_6") (pintype "bidirectional"))
      (node (ref "U30") (pin "4") (pinfunction "SW+2_4") (pintype "bidirectional"))
      (node (ref "U30") (pin "6") (pinfunction "SW+1_6") (pintype "bidirectional"))
      (node (ref "U31") (pin "4") (pinfunction "SW+2_4") (pintype "bidirectional"))
      (node (ref "U31") (pin "6") (pinfunction "SW+1_6") (pintype "bidirectional"))
      (node (ref "U32") (pin "4") (pinfunction "SW+2_4") (pintype "bidirectional"))
      (node (ref "U32") (pin "6") (pinfunction "SW+1_6") (pintype "bidirectional"))
      (node (ref "U33") (pin "4") (pinfunction "SW+2_4") (pintype "bidirectional"))
      (node (ref "U33") (pin "6") (pinfunction "SW+1_6") (pintype "bidirectional"))
      (node (ref "U34") (pin "4") (pinfunction "SW+2_4") (pintype "bidirectional"))
      (node (ref "U34") (pin "6") (pinfunction "SW+1_6") (pintype "bidirectional"))
      (node (ref "U35") (pin "4") (pinfunction "SW+2_4") (pintype "bidirectional"))
      (node (ref "U35") (pin "6") (pinfunction "SW+1_6") (pintype "bidirectional"))
      (node (ref "U36") (pin "4") (pinfunction "SW+2_4") (pintype "bidirectional"))
      (node (ref "U36") (pin "6") (pinfunction "SW+1_6") (pintype "bidirectional"))
      (node (ref "U37") (pin "4") (pinfunction "SW+2_4") (pintype "bidirectional"))
      (node (ref "U37") (pin "6") (pinfunction "SW+1_6") (pintype "bidirectional"))
      (node (ref "U6") (pin "8") (pinfunction "VOUT_8") (pintype "bidirectional"))
    )
    (net (code "35") (name "M8RXD") (class "Default")
      (node (ref "R11") (pin "1") (pinfunction "1_1") (pintype "passive"))
      (node (ref "U4") (pin "1") (pinfunction "TXD_1") (pintype "output"))
    )
    (net (code "36") (name "M8TXD") (class "Default")
      (node (ref "R12") (pin "1") (pinfunction "1_1") (pintype "passive"))
      (node (ref "U4") (pin "5") (pinfunction "RXD_5") (pintype "input"))
    )
    (net (code "37") (name "Net-(F1-Pad2)") (class "Default")
      (node (ref "F1") (pin "2") (pinfunction "2_2") (pintype "passive"))
      (node (ref "X4") (pin "1") (pinfunction "1_1") (pintype "bidirectional"))
    )
    (net (code "38") (name "Net-(F2-Pad2)") (class "Default")
      (node (ref "F2") (pin "2") (pinfunction "2_2") (pintype "passive"))
      (node (ref "J4") (pin "1") (pinfunction "1_1") (pintype "power_in"))
    )
    (net (code "39") (name "Net-(L-A)") (class "Default")
      (node (ref "L") (pin "P$1") (pinfunction "A_P$1") (pintype "passive"))
      (node (ref "R1") (pin "2") (pinfunction "2_2") (pintype "passive"))
    )
    (net (code "40") (name "Net-(RX-A)") (class "Default")
      (node (ref "R7") (pin "1") (pinfunction "1_1") (pintype "passive"))
      (node (ref "RX") (pin "P$1") (pinfunction "A_P$1") (pintype "passive"))
    )
    (net (code "41") (name "Net-(RX-C)") (class "Default")
      (node (ref "RX") (pin "P$2") (pinfunction "C_P$2") (pintype "passive"))
      (node (ref "U4") (pin "23") (pinfunction "GPIO1_23") (pintype "output"))
    )
    (net (code "42") (name "Net-(RX1-A)") (class "Default")
      (node (ref "R3") (pin "1") (pinfunction "1_1") (pintype "passive"))
      (node (ref "RX1") (pin "P$1") (pinfunction "A_P$1") (pintype "passive"))
    )
    (net (code "43") (name "Net-(RX1-C)") (class "Default")
      (node (ref "RX1") (pin "P$2") (pinfunction "C_P$2") (pintype "passive"))
      (node (ref "U2") (pin "23") (pinfunction "GPIO1_23") (pintype "output"))
    )
    (net (code "44") (name "Net-(TX-A)") (class "Default")
      (node (ref "R9") (pin "1") (pinfunction "1_1") (pintype "passive"))
      (node (ref "TX") (pin "P$1") (pinfunction "A_P$1") (pintype "passive"))
    )
    (net (code "45") (name "Net-(TX-C)") (class "Default")
      (node (ref "TX") (pin "P$2") (pinfunction "C_P$2") (pintype "passive"))
      (node (ref "U4") (pin "22") (pinfunction "GPIO0_22") (pintype "output"))
    )
    (net (code "46") (name "Net-(TX1-A)") (class "Default")
      (node (ref "R6") (pin "1") (pinfunction "1_1") (pintype "passive"))
      (node (ref "TX1") (pin "P$1") (pinfunction "A_P$1") (pintype "passive"))
    )
    (net (code "47") (name "Net-(TX1-C)") (class "Default")
      (node (ref "TX1") (pin "P$2") (pinfunction "C_P$2") (pintype "passive"))
      (node (ref "U2") (pin "22") (pinfunction "GPIO0_22") (pintype "output"))
    )
    (net (code "48") (name "Net-(U$28-GA)") (class "Default")
      (node (ref "R38") (pin "2") (pinfunction "2_2") (pintype "passive"))
      (node (ref "U$28") (pin "P$4") (pinfunction "GA_P$4") (pintype "passive"))
    )
    (net (code "49") (name "Net-(U$28-RA)") (class "Default")
      (node (ref "R37") (pin "2") (pinfunction "2_2") (pintype "passive"))
      (node (ref "U$28") (pin "P$2") (pinfunction "RA_P$2") (pintype "passive"))
    )
    (net (code "50") (name "Net-(U1-XTAL1)") (class "Default")
      (node (ref "C2") (pin "2") (pinfunction "2_2") (pintype "passive"))
      (node (ref "Q2") (pin "1") (pinfunction "1_1") (pintype "passive"))
      (node (ref "U1") (pin "34") (pinfunction "XTAL1_34") (pintype "input"))
    )
    (net (code "51") (name "Net-(U1-XTAL2)") (class "Default")
      (node (ref "C3") (pin "2") (pinfunction "2_2") (pintype "passive"))
      (node (ref "Q2") (pin "2") (pinfunction "2_2") (pintype "passive"))
      (node (ref "U1") (pin "33") (pinfunction "XTAL2_33") (pintype "output"))
    )
    (net (code "52") (name "Net-(U2-DTR#)") (class "Default")
      (node (ref "C26") (pin "1") (pinfunction "1_1") (pintype "passive"))
      (node (ref "RESET-EN") (pin "1") (pinfunction "1_1") (pintype "passive"))
      (node (ref "RESET-EN") (pin "2") (pinfunction "2_2") (pintype "passive"))
      (node (ref "U2") (pin "2") (pinfunction "DTR#_2") (pintype "output"))
    )
    (net (code "53") (name "Net-(U3-FB)") (class "Default")
      (node (ref "C6") (pin "+") (pinfunction "+_+") (pintype "passive"))
      (node (ref "L1") (pin "1") (pinfunction "1_1") (pintype "passive"))
      (node (ref "L3") (pin "2") (pinfunction "2_2") (pintype "passive"))
      (node (ref "U3") (pin "4") (pinfunction "FB_4") (pintype "input"))
    )
    (net (code "54") (name "Net-(U3-OUT)") (class "Default")
      (node (ref "D5") (pin "C") (pinfunction "C_C") (pintype "passive"))
      (node (ref "L3") (pin "1") (pinfunction "1_1") (pintype "passive"))
      (node (ref "U3") (pin "8") (pinfunction "OUT_8") (pintype "output"))
    )
    (net (code "55") (name "Net-(U4-RESET#)") (class "Default")
      (node (ref "C16") (pin "2") (pinfunction "2_2") (pintype "passive"))
      (node (ref "R10") (pin "1") (pinfunction "1_1") (pintype "passive"))
      (node (ref "R8") (pin "2") (pinfunction "2_2") (pintype "passive"))
      (node (ref "U4") (pin "19") (pinfunction "RESET#_19") (pintype "input"))
    )
    (net (code "56") (name "Net-(U5-CO)") (class "Default")
      (node (ref "J3") (pin "R") (pinfunction "R_R") (pintype "passive"))
      (node (ref "J3") (pin "T") (pinfunction "T_T") (pintype "passive"))
      (node (ref "U5") (pin "P$4") (pinfunction "CO_P$4") (pintype "bidirectional"))
    )
    (net (code "57") (name "Net-(U5-EM)") (class "Default")
      (node (ref "J3") (pin "S") (pinfunction "S_S") (pintype "passive"))
      (node (ref "U5") (pin "P$3") (pinfunction "EM_P$3") (pintype "bidirectional"))
    )
    (net (code "58") (name "Net-(U5-LED+)") (class "Default")
      (node (ref "R39") (pin "2") (pinfunction "2_2") (pintype "passive"))
      (node (ref "U5") (pin "P$1") (pinfunction "LED+_P$1") (pintype "bidirectional"))
    )
    (net (code "59") (name "Net-(U6-VIN)") (class "Default")
      (node (ref "C8") (pin "1") (pinfunction "1_1") (pintype "passive"))
      (node (ref "L2") (pin "1") (pinfunction "1_1") (pintype "passive"))
      (node (ref "U6") (pin "14") (pinfunction "VIN_14") (pintype "bidirectional"))
    )
    (net (code "60") (name "Net-(U10-LED+)") (class "Default")
      (node (ref "R4") (pin "2") (pinfunction "2_2") (pintype "passive"))
      (node (ref "U10") (pin "1") (pinfunction "LED+_1") (pintype "bidirectional"))
    )
    (net (code "61") (name "Net-(U10-SW-)") (class "Default")
      (node (ref "U10") (pin "5") (pinfunction "SW-_5") (pintype "bidirectional"))
      (node (ref "X1") (pin "1") (pinfunction "F_1") (pintype "passive"))
    )
    (net (code "62") (name "Net-(U11-LED+)") (class "Default")
      (node (ref "R13") (pin "2") (pinfunction "2_2") (pintype "passive"))
      (node (ref "U11") (pin "1") (pinfunction "LED+_1") (pintype "bidirectional"))
    )
    (net (code "63") (name "Net-(U11-SW-)") (class "Default")
      (node (ref "U11") (pin "5") (pinfunction "SW-_5") (pintype "bidirectional"))
      (node (ref "X1") (pin "2") (pinfunction "F_2") (pintype "passive"))
    )
    (net (code "64") (name "Net-(U12-LED+)") (class "Default")
      (node (ref "R14") (pin "2") (pinfunction "2_2") (pintype "passive"))
      (node (ref "U12") (pin "1") (pinfunction "LED+_1") (pintype "bidirectional"))
    )
    (net (code "65") (name "Net-(U12-SW-)") (class "Default")
      (node (ref "U12") (pin "5") (pinfunction "SW-_5") (pintype "bidirectional"))
      (node (ref "X1") (pin "3") (pinfunction "F_3") (pintype "passive"))
    )
    (net (code "66") (name "Net-(U13-LED+)") (class "Default")
      (node (ref "R15") (pin "2") (pinfunction "2_2") (pintype "passive"))
      (node (ref "U13") (pin "1") (pinfunction "LED+_1") (pintype "bidirectional"))
    )
    (net (code "67") (name "Net-(U13-SW-)") (class "Default")
      (node (ref "U13") (pin "5") (pinfunction "SW-_5") (pintype "bidirectional"))
      (node (ref "X1") (pin "4") (pinfunction "F_4") (pintype "passive"))
    )
    (net (code "68") (name "Net-(U14-LED+)") (class "Default")
      (node (ref "R16") (pin "2") (pinfunction "2_2") (pintype "passive"))
      (node (ref "U14") (pin "1") (pinfunction "LED+_1") (pintype "bidirectional"))
    )
    (net (code "69") (name "Net-(U14-SW-)") (class "Default")
      (node (ref "U14") (pin "5") (pinfunction "SW-_5") (pintype "bidirectional"))
      (node (ref "X5") (pin "1") (pinfunction "F_1") (pintype "passive"))
    )
    (net (code "70") (name "Net-(U15-LED+)") (class "Default")
      (node (ref "R17") (pin "2") (pinfunction "2_2") (pintype "passive"))
      (node (ref "U15") (pin "1") (pinfunction "LED+_1") (pintype "bidirectional"))
    )
    (net (code "71") (name "Net-(U15-SW-)") (class "Default")
      (node (ref "U15") (pin "5") (pinfunction "SW-_5") (pintype "bidirectional"))
      (node (ref "X5") (pin "2") (pinfunction "F_2") (pintype "passive"))
    )
    (net (code "72") (name "Net-(U16-LED+)") (class "Default")
      (node (ref "R18") (pin "2") (pinfunction "2_2") (pintype "passive"))
      (node (ref "U16") (pin "1") (pinfunction "LED+_1") (pintype "bidirectional"))
    )
    (net (code "73") (name "Net-(U16-SW-)") (class "Default")
      (node (ref "U16") (pin "5") (pinfunction "SW-_5") (pintype "bidirectional"))
      (node (ref "X5") (pin "3") (pinfunction "F_3") (pintype "passive"))
    )
    (net (code "74") (name "Net-(U17-LED+)") (class "Default")
      (node (ref "R19") (pin "2") (pinfunction "2_2") (pintype "passive"))
      (node (ref "U17") (pin "1") (pinfunction "LED+_1") (pintype "bidirectional"))
    )
    (net (code "75") (name "Net-(U17-SW-)") (class "Default")
      (node (ref "U17") (pin "5") (pinfunction "SW-_5") (pintype "bidirectional"))
      (node (ref "X5") (pin "4") (pinfunction "F_4") (pintype "passive"))
    )
    (net (code "76") (name "Net-(U20-LED+)") (class "Default")
      (node (ref "R20") (pin "2") (pinfunction "2_2") (pintype "passive"))
      (node (ref "U20") (pin "1") (pinfunction "LED+_1") (pintype "bidirectional"))
    )
    (net (code "77") (name "Net-(U20-SW+1)") (class "Default")
      (node (ref "U20") (pin "4") (pinfunction "SW+2_4") (pintype "bidirectional"))
      (node (ref "U20") (pin "6") (pinfunction "SW+1_6") (pintype "bidirectional"))
      (node (ref "X1") (pin "8") (pinfunction "F_8") (pintype "passive"))
      (node (ref "X5") (pin "8") (pinfunction "F_8") (pintype "passive"))
      (node (ref "X6") (pin "8") (pinfunction "F_8") (pintype "passive"))
      (node (ref "X7") (pin "8") (pinfunction "F_8") (pintype "passive"))
    )
    (net (code "78") (name "Net-(U21-LED+)") (class "Default")
      (node (ref "R27") (pin "2") (pinfunction "2_2") (pintype "passive"))
      (node (ref "U21") (pin "1") (pinfunction "LED+_1") (pintype "bidirectional"))
    )
    (net (code "79") (name "Net-(U21-SW+1)") (class "Default")
      (node (ref "U21") (pin "4") (pinfunction "SW+2_4") (pintype "bidirectional"))
      (node (ref "U21") (pin "6") (pinfunction "SW+1_6") (pintype "bidirectional"))
      (node (ref "X1") (pin "15") (pinfunction "F_15") (pintype "passive"))
      (node (ref "X5") (pin "15") (pinfunction "F_15") (pintype "passive"))
      (node (ref "X6") (pin "15") (pinfunction "F_15") (pintype "passive"))
      (node (ref "X7") (pin "15") (pinfunction "F_15") (pintype "passive"))
    )
    (net (code "80") (name "Net-(U22-LED+)") (class "Default")
      (node (ref "R26") (pin "2") (pinfunction "2_2") (pintype "passive"))
      (node (ref "U22") (pin "1") (pinfunction "LED+_1") (pintype "bidirectional"))
    )
    (net (code "81") (name "Net-(U22-SW+1)") (class "Default")
      (node (ref "U22") (pin "4") (pinfunction "SW+2_4") (pintype "bidirectional"))
      (node (ref "U22") (pin "6") (pinfunction "SW+1_6") (pintype "bidirectional"))
      (node (ref "X1") (pin "14") (pinfunction "F_14") (pintype "passive"))
      (node (ref "X5") (pin "14") (pinfunction "F_14") (pintype "passive"))
      (node (ref "X6") (pin "14") (pinfunction "F_14") (pintype "passive"))
      (node (ref "X7") (pin "14") (pinfunction "F_14") (pintype "passive"))
    )
    (net (code "82") (name "Net-(U23-LED+)") (class "Default")
      (node (ref "R25") (pin "2") (pinfunction "2_2") (pintype "passive"))
      (node (ref "U23") (pin "1") (pinfunction "LED+_1") (pintype "bidirectional"))
    )
    (net (code "83") (name "Net-(U23-SW+1)") (class "Default")
      (node (ref "U23") (pin "4") (pinfunction "SW+2_4") (pintype "bidirectional"))
      (node (ref "U23") (pin "6") (pinfunction "SW+1_6") (pintype "bidirectional"))
      (node (ref "X1") (pin "13") (pinfunction "F_13") (pintype "passive"))
      (node (ref "X5") (pin "13") (pinfunction "F_13") (pintype "passive"))
      (node (ref "X6") (pin "13") (pinfunction "F_13") (pintype "passive"))
      (node (ref "X7") (pin "13") (pinfunction "F_13") (pintype "passive"))
    )
    (net (code "84") (name "Net-(U24-LED+)") (class "Default")
      (node (ref "R24") (pin "2") (pinfunction "2_2") (pintype "passive"))
      (node (ref "U24") (pin "1") (pinfunction "LED+_1") (pintype "bidirectional"))
    )
    (net (code "85") (name "Net-(U24-SW+1)") (class "Default")
      (node (ref "U24") (pin "4") (pinfunction "SW+2_4") (pintype "bidirectional"))
      (node (ref "U24") (pin "6") (pinfunction "SW+1_6") (pintype "bidirectional"))
      (node (ref "X1") (pin "12") (pinfunction "F_12") (pintype "passive"))
      (node (ref "X5") (pin "12") (pinfunction "F_12") (pintype "passive"))
      (node (ref "X6") (pin "12") (pinfunction "F_12") (pintype "passive"))
      (node (ref "X7") (pin "12") (pinfunction "F_12") (pintype "passive"))
    )
    (net (code "86") (name "Net-(U25-LED+)") (class "Default")
      (node (ref "R23") (pin "2") (pinfunction "2_2") (pintype "passive"))
      (node (ref "U25") (pin "1") (pinfunction "LED+_1") (pintype "bidirectional"))
    )
    (net (code "87") (name "Net-(U25-SW+1)") (class "Default")
      (node (ref "U25") (pin "4") (pinfunction "SW+2_4") (pintype "bidirectional"))
      (node (ref "U25") (pin "6") (pinfunction "SW+1_6") (pintype "bidirectional"))
      (node (ref "X1") (pin "11") (pinfunction "F_11") (pintype "passive"))
      (node (ref "X5") (pin "11") (pinfunction "F_11") (pintype "passive"))
      (node (ref "X6") (pin "11") (pinfunction "F_11") (pintype "passive"))
      (node (ref "X7") (pin "11") (pinfunction "F_11") (pintype "passive"))
    )
    (net (code "88") (name "Net-(U26-LED+)") (class "Default")
      (node (ref "R22") (pin "2") (pinfunction "2_2") (pintype "passive"))
      (node (ref "U26") (pin "1") (pinfunction "LED+_1") (pintype "bidirectional"))
    )
    (net (code "89") (name "Net-(U26-SW+1)") (class "Default")
      (node (ref "U26") (pin "4") (pinfunction "SW+2_4") (pintype "bidirectional"))
      (node (ref "U26") (pin "6") (pinfunction "SW+1_6") (pintype "bidirectional"))
      (node (ref "X1") (pin "10") (pinfunction "F_10") (pintype "passive"))
      (node (ref "X5") (pin "10") (pinfunction "F_10") (pintype "passive"))
      (node (ref "X6") (pin "10") (pinfunction "F_10") (pintype "passive"))
      (node (ref "X7") (pin "10") (pinfunction "F_10") (pintype "passive"))
    )
    (net (code "90") (name "Net-(U27-LED+)") (class "Default")
      (node (ref "R21") (pin "2") (pinfunction "2_2") (pintype "passive"))
      (node (ref "U27") (pin "1") (pinfunction "LED+_1") (pintype "bidirectional"))
    )
    (net (code "91") (name "Net-(U27-SW+1)") (class "Default")
      (node (ref "U27") (pin "4") (pinfunction "SW+2_4") (pintype "bidirectional"))
      (node (ref "U27") (pin "6") (pinfunction "SW+1_6") (pintype "bidirectional"))
      (node (ref "X1") (pin "9") (pinfunction "F_9") (pintype "passive"))
      (node (ref "X5") (pin "9") (pinfunction "F_9") (pintype "passive"))
      (node (ref "X6") (pin "9") (pinfunction "F_9") (pintype "passive"))
      (node (ref "X7") (pin "9") (pinfunction "F_9") (pintype "passive"))
    )
    (net (code "92") (name "Net-(U30-LED+)") (class "Default")
      (node (ref "R35") (pin "2") (pinfunction "2_2") (pintype "passive"))
      (node (ref "U30") (pin "1") (pinfunction "LED+_1") (pintype "bidirectional"))
    )
    (net (code "93") (name "Net-(U30-SW-)") (class "Default")
      (node (ref "U30") (pin "5") (pinfunction "SW-_5") (pintype "bidirectional"))
      (node (ref "X7") (pin "4") (pinfunction "F_4") (pintype "passive"))
    )
    (net (code "94") (name "Net-(U31-LED+)") (class "Default")
      (node (ref "R34") (pin "2") (pinfunction "2_2") (pintype "passive"))
      (node (ref "U31") (pin "1") (pinfunction "LED+_1") (pintype "bidirectional"))
    )
    (net (code "95") (name "Net-(U31-SW-)") (class "Default")
      (node (ref "U31") (pin "5") (pinfunction "SW-_5") (pintype "bidirectional"))
      (node (ref "X7") (pin "3") (pinfunction "F_3") (pintype "passive"))
    )
    (net (code "96") (name "Net-(U32-LED+)") (class "Default")
      (node (ref "R33") (pin "2") (pinfunction "2_2") (pintype "passive"))
      (node (ref "U32") (pin "1") (pinfunction "LED+_1") (pintype "bidirectional"))
    )
    (net (code "97") (name "Net-(U32-SW-)") (class "Default")
      (node (ref "U32") (pin "5") (pinfunction "SW-_5") (pintype "bidirectional"))
      (node (ref "X7") (pin "2") (pinfunction "F_2") (pintype "passive"))
    )
    (net (code "98") (name "Net-(U33-LED+)") (class "Default")
      (node (ref "R32") (pin "2") (pinfunction "2_2") (pintype "passive"))
      (node (ref "U33") (pin "1") (pinfunction "LED+_1") (pintype "bidirectional"))
    )
    (net (code "99") (name "Net-(U33-SW-)") (class "Default")
      (node (ref "U33") (pin "5") (pinfunction "SW-_5") (pintype "bidirectional"))
      (node (ref "X7") (pin "1") (pinfunction "F_1") (pintype "passive"))
    )
    (net (code "100") (name "Net-(U34-LED+)") (class "Default")
      (node (ref "R31") (pin "2") (pinfunction "2_2") (pintype "passive"))
      (node (ref "U34") (pin "1") (pinfunction "LED+_1") (pintype "bidirectional"))
    )
    (net (code "101") (name "Net-(U34-SW-)") (class "Default")
      (node (ref "U34") (pin "5") (pinfunction "SW-_5") (pintype "bidirectional"))
      (node (ref "X6") (pin "4") (pinfunction "F_4") (pintype "passive"))
    )
    (net (code "102") (name "Net-(U35-LED+)") (class "Default")
      (node (ref "R30") (pin "2") (pinfunction "2_2") (pintype "passive"))
      (node (ref "U35") (pin "1") (pinfunction "LED+_1") (pintype "bidirectional"))
    )
    (net (code "103") (name "Net-(U35-SW-)") (class "Default")
      (node (ref "U35") (pin "5") (pinfunction "SW-_5") (pintype "bidirectional"))
      (node (ref "X6") (pin "3") (pinfunction "F_3") (pintype "passive"))
    )
    (net (code "104") (name "Net-(U36-LED+)") (class "Default")
      (node (ref "R29") (pin "2") (pinfunction "2_2") (pintype "passive"))
      (node (ref "U36") (pin "1") (pinfunction "LED+_1") (pintype "bidirectional"))
    )
    (net (code "105") (name "Net-(U36-SW-)") (class "Default")
      (node (ref "U36") (pin "5") (pinfunction "SW-_5") (pintype "bidirectional"))
      (node (ref "X6") (pin "2") (pinfunction "F_2") (pintype "passive"))
    )
    (net (code "106") (name "Net-(U37-LED+)") (class "Default")
      (node (ref "R28") (pin "2") (pinfunction "2_2") (pintype "passive"))
      (node (ref "U37") (pin "1") (pinfunction "LED+_1") (pintype "bidirectional"))
    )
    (net (code "107") (name "Net-(U37-SW-)") (class "Default")
      (node (ref "U37") (pin "5") (pinfunction "SW-_5") (pintype "bidirectional"))
      (node (ref "X6") (pin "1") (pinfunction "F_1") (pintype "passive"))
    )
    (net (code "108") (name "PB0") (class "Default")
      (node (ref "U1") (pin "19") (pinfunction "(SS/PCINT0)PB0_19") (pintype "bidirectional"))
    )
    (net (code "109") (name "PB1") (class "Default")
      (node (ref "ICSP") (pin "3") (pinfunction "3_3") (pintype "passive"))
      (node (ref "U1") (pin "20") (pinfunction "(SCK/PCINT1)PB1_20") (pintype "bidirectional"))
    )
    (net (code "110") (name "PB2") (class "Default")
      (node (ref "ICSP") (pin "4") (pinfunction "4_4") (pintype "passive"))
      (node (ref "U1") (pin "21") (pinfunction "(MOSI/PCINT2)PB2_21") (pintype "bidirectional"))
    )
    (net (code "111") (name "PB3") (class "Default")
      (node (ref "ICSP") (pin "1") (pinfunction "1_1") (pintype "passive"))
      (node (ref "U1") (pin "22") (pinfunction "(MISO/PCINT3)PB3_22") (pintype "bidirectional"))
    )
    (net (code "112") (name "PB7") (class "Default")
      (node (ref "R1") (pin "1") (pinfunction "1_1") (pintype "passive"))
      (node (ref "U1") (pin "26") (pinfunction "(OC0A/OC1C/PCINT7)PB7_26") (pintype "bidirectional"))
    )
    (net (code "113") (name "PD7") (class "Default")
      (node (ref "U1") (pin "50") (pinfunction "(T0)PD7_50") (pintype "bidirectional"))
    )
    (net (code "114") (name "PH3") (class "Default")
      (node (ref "U1") (pin "15") (pinfunction "PH3(OC4A)_15") (pintype "bidirectional"))
    )
    (net (code "115") (name "PH4") (class "Default")
      (node (ref "U1") (pin "16") (pinfunction "PH4(OC4B)_16") (pintype "bidirectional"))
    )
    (net (code "116") (name "PH5") (class "Default")
      (node (ref "U1") (pin "17") (pinfunction "PH5(OC4C)_17") (pintype "bidirectional"))
    )
    (net (code "117") (name "PH6") (class "Default")
      (node (ref "U1") (pin "18") (pinfunction "PH6(OC2B)_18") (pintype "bidirectional"))
    )
    (net (code "118") (name "PROG_D+") (class "Default")
      (node (ref "J4") (pin "3") (pinfunction "3_3") (pintype "bidirectional"))
      (node (ref "U2") (pin "15") (pinfunction "USBDP_15") (pintype "bidirectional"))
    )
    (net (code "119") (name "PROG_D-") (class "Default")
      (node (ref "J4") (pin "2") (pinfunction "2_2") (pintype "bidirectional"))
      (node (ref "U2") (pin "16") (pinfunction "USBDM_16") (pintype "bidirectional"))
    )
    (net (code "120") (name "RESET") (class "Default")
      (node (ref "C11") (pin "1") (pinfunction "1_1") (pintype "passive"))
      (node (ref "C26") (pin "2") (pinfunction "2_2") (pintype "passive"))
      (node (ref "ICSP") (pin "5") (pinfunction "5_5") (pintype "passive"))
      (node (ref "R5") (pin "1") (pinfunction "1_1") (pintype "passive"))
      (node (ref "S1") (pin "3") (pinfunction "P_3") (pintype "passive"))
      (node (ref "S1") (pin "4") (pinfunction "P1_4") (pintype "passive"))
      (node (ref "U1") (pin "30") (pinfunction "RESET_30") (pintype "input"))
    )
    (net (code "121") (name "RUNNING") (class "Default")
      (node (ref "R38") (pin "1") (pinfunction "1_1") (pintype "passive"))
      (node (ref "U1") (pin "52") (pinfunction "(RD)PG1_52") (pintype "bidirectional"))
    )
    (net (code "122") (name "RXD") (class "Default")
      (node (ref "JP1") (pin "1") (pinfunction "1_1") (pintype "passive"))
      (node (ref "R11") (pin "2") (pinfunction "2_2") (pintype "passive"))
      (node (ref "U1") (pin "63") (pinfunction "PJ0(RXD3/PCINT9)_63") (pintype "bidirectional"))
    )
    (net (code "123") (name "RXD1") (class "Default")
      (node (ref "U1") (pin "45") (pinfunction "(RXD1/INT2)PD2_45") (pintype "bidirectional"))
    )
    (net (code "124") (name "RXD2") (class "Default")
      (node (ref "JP3") (pin "6") (pinfunction "6_6") (pintype "passive"))
      (node (ref "U1") (pin "12") (pinfunction "PH0(RXD2)_12") (pintype "bidirectional"))
    )
    (net (code "125") (name "RXDP") (class "Default")
      (node (ref "JP2") (pin "4") (pinfunction "4_4") (pintype "passive"))
      (node (ref "R40") (pin "1") (pinfunction "1_1") (pintype "passive"))
      (node (ref "U2") (pin "1") (pinfunction "TXD_1") (pintype "output"))
    )
    (net (code "126") (name "RXD_PROG") (class "Default")
      (node (ref "R40") (pin "2") (pinfunction "2_2") (pintype "passive"))
      (node (ref "U1") (pin "2") (pinfunction "(RXD0/PCIN8)PE0_2") (pintype "bidirectional"))
    )
    (net (code "127") (name "SCL") (class "Default")
      (node (ref "JP3") (pin "1") (pinfunction "1_1") (pintype "passive"))
      (node (ref "U1") (pin "43") (pinfunction "(SCL/INT0)PD0_43") (pintype "bidirectional"))
    )
    (net (code "128") (name "SDA") (class "Default")
      (node (ref "JP3") (pin "3") (pinfunction "3_3") (pintype "passive"))
      (node (ref "U1") (pin "44") (pinfunction "(SDA/INT1)PD1_44") (pintype "bidirectional"))
    )
    (net (code "129") (name "SHUTTER") (class "Default")
      (node (ref "R39") (pin "1") (pinfunction "1_1") (pintype "passive"))
      (node (ref "U1") (pin "51") (pinfunction "(WR)PG0_51") (pintype "bidirectional"))
    )
    (net (code "130") (name "SW1") (class "Default")
      (node (ref "C46") (pin "1") (pinfunction "1_1") (pintype "passive"))
      (node (ref "JP3") (pin "7") (pinfunction "7_7") (pintype "passive"))
      (node (ref "R46") (pin "2") (pinfunction "2_2") (pintype "passive"))
      (node (ref "U1") (pin "89") (pinfunction "PK0(ADC8/PCINT16)_89") (pintype "bidirectional"))
    )
    (net (code "131") (name "SW2") (class "Default")
      (node (ref "C45") (pin "1") (pinfunction "1_1") (pintype "passive"))
      (node (ref "JP3") (pin "9") (pinfunction "9_9") (pintype "passive"))
      (node (ref "R45") (pin "2") (pinfunction "2_2") (pintype "passive"))
      (node (ref "U1") (pin "88") (pinfunction "PK1(ADC9/PCINT17)_88") (pintype "bidirectional"))
    )
    (net (code "132") (name "SW3") (class "Default")
      (node (ref "C44") (pin "1") (pinfunction "1_1") (pintype "passive"))
      (node (ref "JP3") (pin "11") (pinfunction "11_11") (pintype "passive"))
      (node (ref "R44") (pin "2") (pinfunction "2_2") (pintype "passive"))
      (node (ref "U1") (pin "87") (pinfunction "PK2(ADC10/PCINT18)_87") (pintype "bidirectional"))
    )
    (net (code "133") (name "SW4") (class "Default")
      (node (ref "C43") (pin "1") (pinfunction "1_1") (pintype "passive"))
      (node (ref "JP3") (pin "13") (pinfunction "13_13") (pintype "passive"))
      (node (ref "R43") (pin "2") (pinfunction "2_2") (pintype "passive"))
      (node (ref "U1") (pin "86") (pinfunction "PK3(ADC11/PCINT19)_86") (pintype "bidirectional"))
    )
    (net (code "134") (name "SW5") (class "Default")
      (node (ref "C42") (pin "1") (pinfunction "1_1") (pintype "passive"))
      (node (ref "JP3") (pin "15") (pinfunction "15_15") (pintype "passive"))
      (node (ref "R42") (pin "2") (pinfunction "2_2") (pintype "passive"))
      (node (ref "U1") (pin "85") (pinfunction "PK4(ADC12/PCINT20)_85") (pintype "bidirectional"))
    )
    (net (code "135") (name "TXD") (class "Default")
      (node (ref "JP1") (pin "2") (pinfunction "2_2") (pintype "passive"))
      (node (ref "R12") (pin "2") (pinfunction "2_2") (pintype "passive"))
      (node (ref "U1") (pin "64") (pinfunction "PJ1(TXD3/PCINT10)_64") (pintype "bidirectional"))
    )
    (net (code "136") (name "TXD1") (class "Default")
      (node (ref "U1") (pin "46") (pinfunction "(TXD1/INT3)PD3_46") (pintype "bidirectional"))
    )
    (net (code "137") (name "TXD2") (class "Default")
      (node (ref "JP3") (pin "5") (pinfunction "5_5") (pintype "passive"))
      (node (ref "U1") (pin "13") (pinfunction "PH1(TXD2)_13") (pintype "bidirectional"))
    )
    (net (code "138") (name "TXDP") (class "Default")
      (node (ref "JP2") (pin "5") (pinfunction "5_5") (pintype "passive"))
      (node (ref "R41") (pin "1") (pinfunction "1_1") (pintype "passive"))
      (node (ref "U2") (pin "5") (pinfunction "RXD_5") (pintype "input"))
    )
    (net (code "139") (name "TXD_PROG") (class "Default")
      (node (ref "R41") (pin "2") (pinfunction "2_2") (pintype "passive"))
      (node (ref "U1") (pin "3") (pinfunction "(TXD0)PE1_3") (pintype "bidirectional"))
    )
    (net (code "140") (name "USBPROGVCC") (class "Default")
      (node (ref "C18") (pin "1") (pinfunction "1_1") (pintype "passive"))
      (node (ref "C25") (pin "1") (pinfunction "1_1") (pintype "passive"))
      (node (ref "C30") (pin "1") (pinfunction "1_1") (pintype "passive"))
      (node (ref "C31") (pin "1") (pinfunction "1_1") (pintype "passive"))
      (node (ref "C32") (pin "1") (pinfunction "1_1") (pintype "passive"))
      (node (ref "D4") (pin "2") (pinfunction "A2_2") (pintype "passive"))
      (node (ref "F2") (pin "1") (pinfunction "1_1") (pintype "passive"))
      (node (ref "JP2") (pin "3") (pinfunction "3_3") (pintype "passive"))
      (node (ref "R3") (pin "2") (pinfunction "2_2") (pintype "passive"))
      (node (ref "R6") (pin "2") (pinfunction "2_2") (pintype "passive"))
      (node (ref "U2") (pin "19") (pinfunction "RESET#_19") (pintype "input"))
      (node (ref "U2") (pin "20") (pinfunction "VCC5I_20") (pintype "power_in"))
      (node (ref "U2") (pin "4") (pinfunction "VCCIO_4") (pintype "power_in"))
    )
    (net (code "141") (name "USBVCC") (class "Default")
      (node (ref "C14") (pin "1") (pinfunction "1_1") (pintype "passive"))
      (node (ref "D4") (pin "1") (pinfunction "A1_1") (pintype "passive"))
      (node (ref "F1") (pin "1") (pinfunction "1_1") (pintype "passive"))
      (node (ref "R7") (pin "2") (pinfunction "2_2") (pintype "passive"))
      (node (ref "R8") (pin "1") (pinfunction "1_1") (pintype "passive"))
      (node (ref "R9") (pin "2") (pinfunction "2_2") (pintype "passive"))
    )
    (net (code "142") (name "VIN") (class "Default")
      (node (ref "C12") (pin "1") (pinfunction "1_1") (pintype "passive"))
      (node (ref "C5") (pin "+") (pinfunction "+_+") (pintype "passive"))
      (node (ref "D2") (pin "1") (pinfunction "C_1") (pintype "passive"))
      (node (ref "L2") (pin "2") (pinfunction "2_2") (pintype "passive"))
      (node (ref "U3") (pin "7") (pinfunction "VIN_7") (pintype "power_in"))
    )
    (net (code "143") (name "VPWR") (class "Default")
      (node (ref "D2") (pin "2") (pinfunction "A_2") (pintype "passive"))
      (node (ref "J1") (pin "3") (pinfunction "3_3") (pintype "passive"))
    )
    (net (code "144") (name "unconnected-(J2-B-Pad4)") (class "Default")
      (node (ref "J2") (pin "4") (pinfunction "B_4") (pintype "passive"))
    )
    (net (code "145") (name "unconnected-(J2-R-Pad2)") (class "Default")
      (node (ref "J2") (pin "2") (pinfunction "R_2") (pintype "passive"))
    )
    (net (code "146") (name "unconnected-(J4-Pad4)") (class "Default")
      (node (ref "J4") (pin "4") (pinfunction "4_4") (pintype "bidirectional"))
    )
    (net (code "147") (name "unconnected-(JP2-Pad2)") (class "Default")
      (node (ref "JP2") (pin "2") (pinfunction "2_2") (pintype "passive"))
    )
    (net (code "148") (name "unconnected-(JP2-Pad6)") (class "Default")
      (node (ref "JP2") (pin "6") (pinfunction "6_6") (pintype "passive"))
    )
    (net (code "149") (name "unconnected-(JP7-Pad1)") (class "Default")
      (node (ref "JP7") (pin "1") (pinfunction "1_1") (pintype "passive"))
    )
    (net (code "150") (name "unconnected-(JP8-Pad1)") (class "Default")
      (node (ref "JP8") (pin "1") (pinfunction "1_1") (pintype "passive"))
    )
    (net (code "151") (name "unconnected-(JP9-Pad1)") (class "Default")
      (node (ref "JP9") (pin "1") (pinfunction "1_1") (pintype "passive"))
    )
    (net (code "152") (name "unconnected-(U1-(ADC0)PF0-Pad97)") (class "Default")
      (node (ref "U1") (pin "97") (pinfunction "(ADC0)PF0_97") (pintype "bidirectional"))
    )
    (net (code "153") (name "unconnected-(U1-(ADC1)PF1-Pad96)") (class "Default")
      (node (ref "U1") (pin "96") (pinfunction "(ADC1)PF1_96") (pintype "bidirectional"))
    )
    (net (code "154") (name "unconnected-(U1-(ADC2)PF2-Pad95)") (class "Default")
      (node (ref "U1") (pin "95") (pinfunction "(ADC2)PF2_95") (pintype "bidirectional"))
    )
    (net (code "155") (name "unconnected-(U1-(ADC3)PF3-Pad94)") (class "Default")
      (node (ref "U1") (pin "94") (pinfunction "(ADC3)PF3_94") (pintype "bidirectional"))
    )
    (net (code "156") (name "unconnected-(U1-(ADC4{slash}TCK)PF4-Pad93)") (class "Default")
      (node (ref "U1") (pin "93") (pinfunction "(ADC4/TCK)PF4_93") (pintype "bidirectional"))
    )
    (net (code "157") (name "unconnected-(U1-(ADC5{slash}TMS)PF5-Pad92)") (class "Default")
      (node (ref "U1") (pin "92") (pinfunction "(ADC5/TMS)PF5_92") (pintype "bidirectional"))
    )
    (net (code "158") (name "unconnected-(U1-(ADC6{slash}TDO)PF6-Pad91)") (class "Default")
      (node (ref "U1") (pin "91") (pinfunction "(ADC6/TDO)PF6_91") (pintype "bidirectional"))
    )
    (net (code "159") (name "unconnected-(U1-(ADC7{slash}TDI)PF7-Pad90)") (class "Default")
      (node (ref "U1") (pin "90") (pinfunction "(ADC7/TDI)PF7_90") (pintype "bidirectional"))
    )
    (net (code "160") (name "unconnected-(U1-(CLKO{slash}ICP3{slash}INT7)PE7-Pad9)") (class "Default")
      (node (ref "U1") (pin "9") (pinfunction "(CLKO/ICP3/INT7)PE7_9") (pintype "bidirectional"))
    )
    (net (code "161") (name "unconnected-(U1-(ICP1)PD4-Pad47)") (class "Default")
      (node (ref "U1") (pin "47") (pinfunction "(ICP1)PD4_47") (pintype "bidirectional"))
    )
    (net (code "162") (name "unconnected-(U1-(OC0B)PG5-Pad1)") (class "Default")
      (node (ref "U1") (pin "1") (pinfunction "(OC0B)PG5_1") (pintype "bidirectional"))
    )
    (net (code "163") (name "unconnected-(U1-(OC1A{slash}PCINT5)PB5-Pad24)") (class "Default")
      (node (ref "U1") (pin "24") (pinfunction "(OC1A/PCINT5)PB5_24") (pintype "bidirectional"))
    )
    (net (code "164") (name "unconnected-(U1-(OC1B{slash}PCINT6)PB6-Pad25)") (class "Default")
      (node (ref "U1") (pin "25") (pinfunction "(OC1B/PCINT6)PB6_25") (pintype "bidirectional"))
    )
    (net (code "165") (name "unconnected-(U1-(OC2A{slash}PCINT4)PB4-Pad23)") (class "Default")
      (node (ref "U1") (pin "23") (pinfunction "(OC2A/PCINT4)PB4_23") (pintype "bidirectional"))
    )
    (net (code "166") (name "unconnected-(U1-(OC3A{slash}AIN1)PE3-Pad5)") (class "Default")
      (node (ref "U1") (pin "5") (pinfunction "(OC3A/AIN1)PE3_5") (pintype "bidirectional"))
    )
    (net (code "167") (name "unconnected-(U1-(OC3B{slash}INT4)PE4-Pad6)") (class "Default")
      (node (ref "U1") (pin "6") (pinfunction "(OC3B/INT4)PE4_6") (pintype "bidirectional"))
    )
    (net (code "168") (name "unconnected-(U1-(OC3C{slash}INT5)PE5-Pad7)") (class "Default")
      (node (ref "U1") (pin "7") (pinfunction "(OC3C/INT5)PE5_7") (pintype "bidirectional"))
    )
    (net (code "169") (name "unconnected-(U1-(T1)PD6-Pad49)") (class "Default")
      (node (ref "U1") (pin "49") (pinfunction "(T1)PD6_49") (pintype "bidirectional"))
    )
    (net (code "170") (name "unconnected-(U1-(T3{slash}INT6)PE6-Pad8)") (class "Default")
      (node (ref "U1") (pin "8") (pinfunction "(T3/INT6)PE6_8") (pintype "bidirectional"))
    )
    (net (code "171") (name "unconnected-(U1-(TOSC1)PG4-Pad29)") (class "Default")
      (node (ref "U1") (pin "29") (pinfunction "(TOSC1)PG4_29") (pintype "bidirectional"))
    )
    (net (code "172") (name "unconnected-(U1-(TOSC2)PG3-Pad28)") (class "Default")
      (node (ref "U1") (pin "28") (pinfunction "(TOSC2)PG3_28") (pintype "bidirectional"))
    )
    (net (code "173") (name "unconnected-(U1-(XCK0{slash}AIN0)PE2-Pad4)") (class "Default")
      (node (ref "U1") (pin "4") (pinfunction "(XCK0/AIN0)PE2_4") (pintype "bidirectional"))
    )
    (net (code "174") (name "unconnected-(U1-(XCK1)PD5-Pad48)") (class "Default")
      (node (ref "U1") (pin "48") (pinfunction "(XCK1)PD5_48") (pintype "bidirectional"))
    )
    (net (code "175") (name "unconnected-(U1-PH2(XCK2)-Pad14)") (class "Default")
      (node (ref "U1") (pin "14") (pinfunction "PH2(XCK2)_14") (pintype "bidirectional"))
    )
    (net (code "176") (name "unconnected-(U1-PH7(T4)-Pad27)") (class "Default")
      (node (ref "U1") (pin "27") (pinfunction "PH7(T4)_27") (pintype "bidirectional"))
    )
    (net (code "177") (name "unconnected-(U1-PJ2(XCK3{slash}PCINT11)-Pad65)") (class "Default")
      (node (ref "U1") (pin "65") (pinfunction "PJ2(XCK3/PCINT11)_65") (pintype "bidirectional"))
    )
    (net (code "178") (name "unconnected-(U1-PJ3(PCINT12)-Pad66)") (class "Default")
      (node (ref "U1") (pin "66") (pinfunction "PJ3(PCINT12)_66") (pintype "bidirectional"))
    )
    (net (code "179") (name "unconnected-(U1-PJ4(PCINT13)-Pad67)") (class "Default")
      (node (ref "U1") (pin "67") (pinfunction "PJ4(PCINT13)_67") (pintype "bidirectional"))
    )
    (net (code "180") (name "unconnected-(U1-PJ5(PCINT14)-Pad68)") (class "Default")
      (node (ref "U1") (pin "68") (pinfunction "PJ5(PCINT14)_68") (pintype "bidirectional"))
    )
    (net (code "181") (name "unconnected-(U1-PJ6(PCINT15)-Pad69)") (class "Default")
      (node (ref "U1") (pin "69") (pinfunction "PJ6(PCINT15)_69") (pintype "bidirectional"))
    )
    (net (code "182") (name "unconnected-(U1-PJ7-Pad79)") (class "Default")
      (node (ref "U1") (pin "79") (pinfunction "PJ7_79") (pintype "bidirectional"))
    )
    (net (code "183") (name "unconnected-(U1-PK5(ADC13{slash}PCINT21)-Pad84)") (class "Default")
      (node (ref "U1") (pin "84") (pinfunction "PK5(ADC13/PCINT21)_84") (pintype "bidirectional"))
    )
    (net (code "184") (name "unconnected-(U1-PK6(ADC14{slash}PCINT22)-Pad83)") (class "Default")
      (node (ref "U1") (pin "83") (pinfunction "PK6(ADC14/PCINT22)_83") (pintype "bidirectional"))
    )
    (net (code "185") (name "unconnected-(U1-PK7(ADC15{slash}PCINT23)-Pad82)") (class "Default")
      (node (ref "U1") (pin "82") (pinfunction "PK7(ADC15/PCINT23)_82") (pintype "bidirectional"))
    )
    (net (code "186") (name "unconnected-(U2-AVCC-NC-Pad24)") (class "Default")
      (node (ref "U2") (pin "24") (pinfunction "AVCC-NC_24") (pintype "no_connect"))
    )
    (net (code "187") (name "unconnected-(U2-CTS#-Pad11)") (class "Default")
      (node (ref "U2") (pin "11") (pinfunction "CTS#_11") (pintype "input"))
    )
    (net (code "188") (name "unconnected-(U2-DCD#-Pad10)") (class "Default")
      (node (ref "U2") (pin "10") (pinfunction "DCD#_10") (pintype "input"))
    )
    (net (code "189") (name "unconnected-(U2-DSR#-Pad9)") (class "Default")
      (node (ref "U2") (pin "9") (pinfunction "DSR#_9") (pintype "input"))
    )
    (net (code "190") (name "unconnected-(U2-GPIO2-Pad13)") (class "Default")
      (node (ref "U2") (pin "13") (pinfunction "GPIO2_13") (pintype "output"))
    )
    (net (code "191") (name "unconnected-(U2-GPIO3-Pad14)") (class "Default")
      (node (ref "U2") (pin "14") (pinfunction "GPIO3_14") (pintype "input"))
    )
    (net (code "192") (name "unconnected-(U2-OSCI-Pad27)") (class "Default")
      (node (ref "U2") (pin "27") (pinfunction "OSCI_27") (pintype "input"))
    )
    (net (code "193") (name "unconnected-(U2-OSCO-Pad28)") (class "Default")
      (node (ref "U2") (pin "28") (pinfunction "OSCO_28") (pintype "output"))
    )
    (net (code "194") (name "unconnected-(U2-RI#-Pad6)") (class "Default")
      (node (ref "U2") (pin "6") (pinfunction "RI#_6") (pintype "input"))
    )
    (net (code "195") (name "unconnected-(U2-RTS#-Pad3)") (class "Default")
      (node (ref "U2") (pin "3") (pinfunction "RTS#_3") (pintype "output"))
    )
    (net (code "196") (name "unconnected-(U2-SLEEP#-Pad12)") (class "Default")
      (node (ref "U2") (pin "12") (pinfunction "SLEEP#_12") (pintype "input"))
    )
    (net (code "197") (name "unconnected-(U2-VCC3I-NC-Pad8)") (class "Default")
      (node (ref "U2") (pin "8") (pinfunction "VCC3I-NC_8") (pintype "no_connect"))
    )
    (net (code "198") (name "unconnected-(U3-NC-Pad3)") (class "Default")
      (node (ref "U3") (pin "3") (pinfunction "NC_3") (pintype "no_connect"))
    )
    (net (code "199") (name "unconnected-(U3-NC_2-Pad1)") (class "Default")
      (node (ref "U3") (pin "1") (pinfunction "NC_2_1") (pintype "no_connect"))
    )
    (net (code "200") (name "unconnected-(U3-NC_3-Pad2)") (class "Default")
      (node (ref "U3") (pin "2") (pinfunction "NC_3_2") (pintype "no_connect"))
    )
    (net (code "201") (name "unconnected-(U4-AVCC-NC-Pad24)") (class "Default")
      (node (ref "U4") (pin "24") (pinfunction "AVCC-NC_24") (pintype "no_connect"))
    )
    (net (code "202") (name "unconnected-(U4-CTS#-Pad11)") (class "Default")
      (node (ref "U4") (pin "11") (pinfunction "CTS#_11") (pintype "input"))
    )
    (net (code "203") (name "unconnected-(U4-DCD#-Pad10)") (class "Default")
      (node (ref "U4") (pin "10") (pinfunction "DCD#_10") (pintype "input"))
    )
    (net (code "204") (name "unconnected-(U4-DSR#-Pad9)") (class "Default")
      (node (ref "U4") (pin "9") (pinfunction "DSR#_9") (pintype "input"))
    )
    (net (code "205") (name "unconnected-(U4-DTR#-Pad2)") (class "Default")
      (node (ref "U4") (pin "2") (pinfunction "DTR#_2") (pintype "output"))
    )
    (net (code "206") (name "unconnected-(U4-GPIO2-Pad13)") (class "Default")
      (node (ref "U4") (pin "13") (pinfunction "GPIO2_13") (pintype "output"))
    )
    (net (code "207") (name "unconnected-(U4-GPIO3-Pad14)") (class "Default")
      (node (ref "U4") (pin "14") (pinfunction "GPIO3_14") (pintype "input"))
    )
    (net (code "208") (name "unconnected-(U4-OSCI-Pad27)") (class "Default")
      (node (ref "U4") (pin "27") (pinfunction "OSCI_27") (pintype "input"))
    )
    (net (code "209") (name "unconnected-(U4-OSCO-Pad28)") (class "Default")
      (node (ref "U4") (pin "28") (pinfunction "OSCO_28") (pintype "output"))
    )
    (net (code "210") (name "unconnected-(U4-RI#-Pad6)") (class "Default")
      (node (ref "U4") (pin "6") (pinfunction "RI#_6") (pintype "input"))
    )
    (net (code "211") (name "unconnected-(U4-RTS#-Pad3)") (class "Default")
      (node (ref "U4") (pin "3") (pinfunction "RTS#_3") (pintype "output"))
    )
    (net (code "212") (name "unconnected-(U4-SLEEP#-Pad12)") (class "Default")
      (node (ref "U4") (pin "12") (pinfunction "SLEEP#_12") (pintype "input"))
    )
    (net (code "213") (name "unconnected-(U4-VCC3I-NC-Pad8)") (class "Default")
      (node (ref "U4") (pin "8") (pinfunction "VCC3I-NC_8") (pintype "no_connect"))
    )
    (net (code "214") (name "unconnected-(U6-CONTROL-Pad2)") (class "Default")
      (node (ref "U6") (pin "2") (pinfunction "CONTROL_2") (pintype "bidirectional"))
    )
    (net (code "215") (name "unconnected-(U10-N{slash}C-Pad3)") (class "Default")
      (node (ref "U10") (pin "3") (pinfunction "N/C_3") (pintype "no_connect"))
    )
    (net (code "216") (name "unconnected-(U11-N{slash}C-Pad3)") (class "Default")
      (node (ref "U11") (pin "3") (pinfunction "N/C_3") (pintype "no_connect"))
    )
    (net (code "217") (name "unconnected-(U12-N{slash}C-Pad3)") (class "Default")
      (node (ref "U12") (pin "3") (pinfunction "N/C_3") (pintype "no_connect"))
    )
    (net (code "218") (name "unconnected-(U13-N{slash}C-Pad3)") (class "Default")
      (node (ref "U13") (pin "3") (pinfunction "N/C_3") (pintype "no_connect"))
    )
    (net (code "219") (name "unconnected-(U14-N{slash}C-Pad3)") (class "Default")
      (node (ref "U14") (pin "3") (pinfunction "N/C_3") (pintype "no_connect"))
    )
    (net (code "220") (name "unconnected-(U15-N{slash}C-Pad3)") (class "Default")
      (node (ref "U15") (pin "3") (pinfunction "N/C_3") (pintype "no_connect"))
    )
    (net (code "221") (name "unconnected-(U16-N{slash}C-Pad3)") (class "Default")
      (node (ref "U16") (pin "3") (pinfunction "N/C_3") (pintype "no_connect"))
    )
    (net (code "222") (name "unconnected-(U17-N{slash}C-Pad3)") (class "Default")
      (node (ref "U17") (pin "3") (pinfunction "N/C_3") (pintype "no_connect"))
    )
    (net (code "223") (name "unconnected-(U20-N{slash}C-Pad3)") (class "Default")
      (node (ref "U20") (pin "3") (pinfunction "N/C_3") (pintype "no_connect"))
    )
    (net (code "224") (name "unconnected-(U21-N{slash}C-Pad3)") (class "Default")
      (node (ref "U21") (pin "3") (pinfunction "N/C_3") (pintype "no_connect"))
    )
    (net (code "225") (name "unconnected-(U22-N{slash}C-Pad3)") (class "Default")
      (node (ref "U22") (pin "3") (pinfunction "N/C_3") (pintype "no_connect"))
    )
    (net (code "226") (name "unconnected-(U23-N{slash}C-Pad3)") (class "Default")
      (node (ref "U23") (pin "3") (pinfunction "N/C_3") (pintype "no_connect"))
    )
    (net (code "227") (name "unconnected-(U24-N{slash}C-Pad3)") (class "Default")
      (node (ref "U24") (pin "3") (pinfunction "N/C_3") (pintype "no_connect"))
    )
    (net (code "228") (name "unconnected-(U25-N{slash}C-Pad3)") (class "Default")
      (node (ref "U25") (pin "3") (pinfunction "N/C_3") (pintype "no_connect"))
    )
    (net (code "229") (name "unconnected-(U26-N{slash}C-Pad3)") (class "Default")
      (node (ref "U26") (pin "3") (pinfunction "N/C_3") (pintype "no_connect"))
    )
    (net (code "230") (name "unconnected-(U27-N{slash}C-Pad3)") (class "Default")
      (node (ref "U27") (pin "3") (pinfunction "N/C_3") (pintype "no_connect"))
    )
    (net (code "231") (name "unconnected-(U30-N{slash}C-Pad3)") (class "Default")
      (node (ref "U30") (pin "3") (pinfunction "N/C_3") (pintype "no_connect"))
    )
    (net (code "232") (name "unconnected-(U31-N{slash}C-Pad3)") (class "Default")
      (node (ref "U31") (pin "3") (pinfunction "N/C_3") (pintype "no_connect"))
    )
    (net (code "233") (name "unconnected-(U32-N{slash}C-Pad3)") (class "Default")
      (node (ref "U32") (pin "3") (pinfunction "N/C_3") (pintype "no_connect"))
    )
    (net (code "234") (name "unconnected-(U33-N{slash}C-Pad3)") (class "Default")
      (node (ref "U33") (pin "3") (pinfunction "N/C_3") (pintype "no_connect"))
    )
    (net (code "235") (name "unconnected-(U34-N{slash}C-Pad3)") (class "Default")
      (node (ref "U34") (pin "3") (pinfunction "N/C_3") (pintype "no_connect"))
    )
    (net (code "236") (name "unconnected-(U35-N{slash}C-Pad3)") (class "Default")
      (node (ref "U35") (pin "3") (pinfunction "N/C_3") (pintype "no_connect"))
    )
    (net (code "237") (name "unconnected-(U36-N{slash}C-Pad3)") (class "Default")
      (node (ref "U36") (pin "3") (pinfunction "N/C_3") (pintype "no_connect"))
    )
    (net (code "238") (name "unconnected-(U37-N{slash}C-Pad3)") (class "Default")
      (node (ref "U37") (pin "3") (pinfunction "N/C_3") (pintype "no_connect"))
    )
    (net (code "239") (name "unconnected-(X1-PadG1)") (class "Default")
      (node (ref "X1") (pin "G1") (pinfunction "G1_G1") (pintype "passive"))
    )
    (net (code "240") (name "unconnected-(X1-PadG2)") (class "Default")
      (node (ref "X1") (pin "G2") (pinfunction "G2_G2") (pintype "passive"))
    )
    (net (code "241") (name "unconnected-(X1K-F-Pad5)") (class "Default")
      (node (ref "X1") (pin "5") (pinfunction "F_5") (pintype "passive"))
    )
    (net (code "242") (name "unconnected-(X1L-F-Pad6)") (class "Default")
      (node (ref "X1") (pin "6") (pinfunction "F_6") (pintype "passive"))
    )
    (net (code "243") (name "unconnected-(X1M-F-Pad7)") (class "Default")
      (node (ref "X1") (pin "7") (pinfunction "F_7") (pintype "passive"))
    )
    (net (code "244") (name "unconnected-(X5-PadG1)") (class "Default")
      (node (ref "X5") (pin "G1") (pinfunction "G1_G1") (pintype "passive"))
    )
    (net (code "245") (name "unconnected-(X5-PadG2)") (class "Default")
      (node (ref "X5") (pin "G2") (pinfunction "G2_G2") (pintype "passive"))
    )
    (net (code "246") (name "unconnected-(X5K-F-Pad5)") (class "Default")
      (node (ref "X5") (pin "5") (pinfunction "F_5") (pintype "passive"))
    )
    (net (code "247") (name "unconnected-(X5L-F-Pad6)") (class "Default")
      (node (ref "X5") (pin "6") (pinfunction "F_6") (pintype "passive"))
    )
    (net (code "248") (name "unconnected-(X5M-F-Pad7)") (class "Default")
      (node (ref "X5") (pin "7") (pinfunction "F_7") (pintype "passive"))
    )
    (net (code "249") (name "unconnected-(X6-PadG1)") (class "Default")
      (node (ref "X6") (pin "G1") (pinfunction "G1_G1") (pintype "passive"))
    )
    (net (code "250") (name "unconnected-(X6-PadG2)") (class "Default")
      (node (ref "X6") (pin "G2") (pinfunction "G2_G2") (pintype "passive"))
    )
    (net (code "251") (name "unconnected-(X6K-F-Pad5)") (class "Default")
      (node (ref "X6") (pin "5") (pinfunction "F_5") (pintype "passive"))
    )
    (net (code "252") (name "unconnected-(X6L-F-Pad6)") (class "Default")
      (node (ref "X6") (pin "6") (pinfunction "F_6") (pintype "passive"))
    )
    (net (code "253") (name "unconnected-(X6M-F-Pad7)") (class "Default")
      (node (ref "X6") (pin "7") (pinfunction "F_7") (pintype "passive"))
    )
    (net (code "254") (name "unconnected-(X7-PadG1)") (class "Default")
      (node (ref "X7") (pin "G1") (pinfunction "G1_G1") (pintype "passive"))
    )
    (net (code "255") (name "unconnected-(X7-PadG2)") (class "Default")
      (node (ref "X7") (pin "G2") (pinfunction "G2_G2") (pintype "passive"))
    )
    (net (code "256") (name "unconnected-(X7K-F-Pad5)") (class "Default")
      (node (ref "X7") (pin "5") (pinfunction "F_5") (pintype "passive"))
    )
    (net (code "257") (name "unconnected-(X7L-F-Pad6)") (class "Default")
      (node (ref "X7") (pin "6") (pinfunction "F_6") (pintype "passive"))
    )
    (net (code "258") (name "unconnected-(X7M-F-Pad7)") (class "Default")
      (node (ref "X7") (pin "7") (pinfunction "F_7") (pintype "passive"))
    )
  )
)
